# 10x15_Matrix.net
KiCad netlist of a schematic drawn in Altium Designer
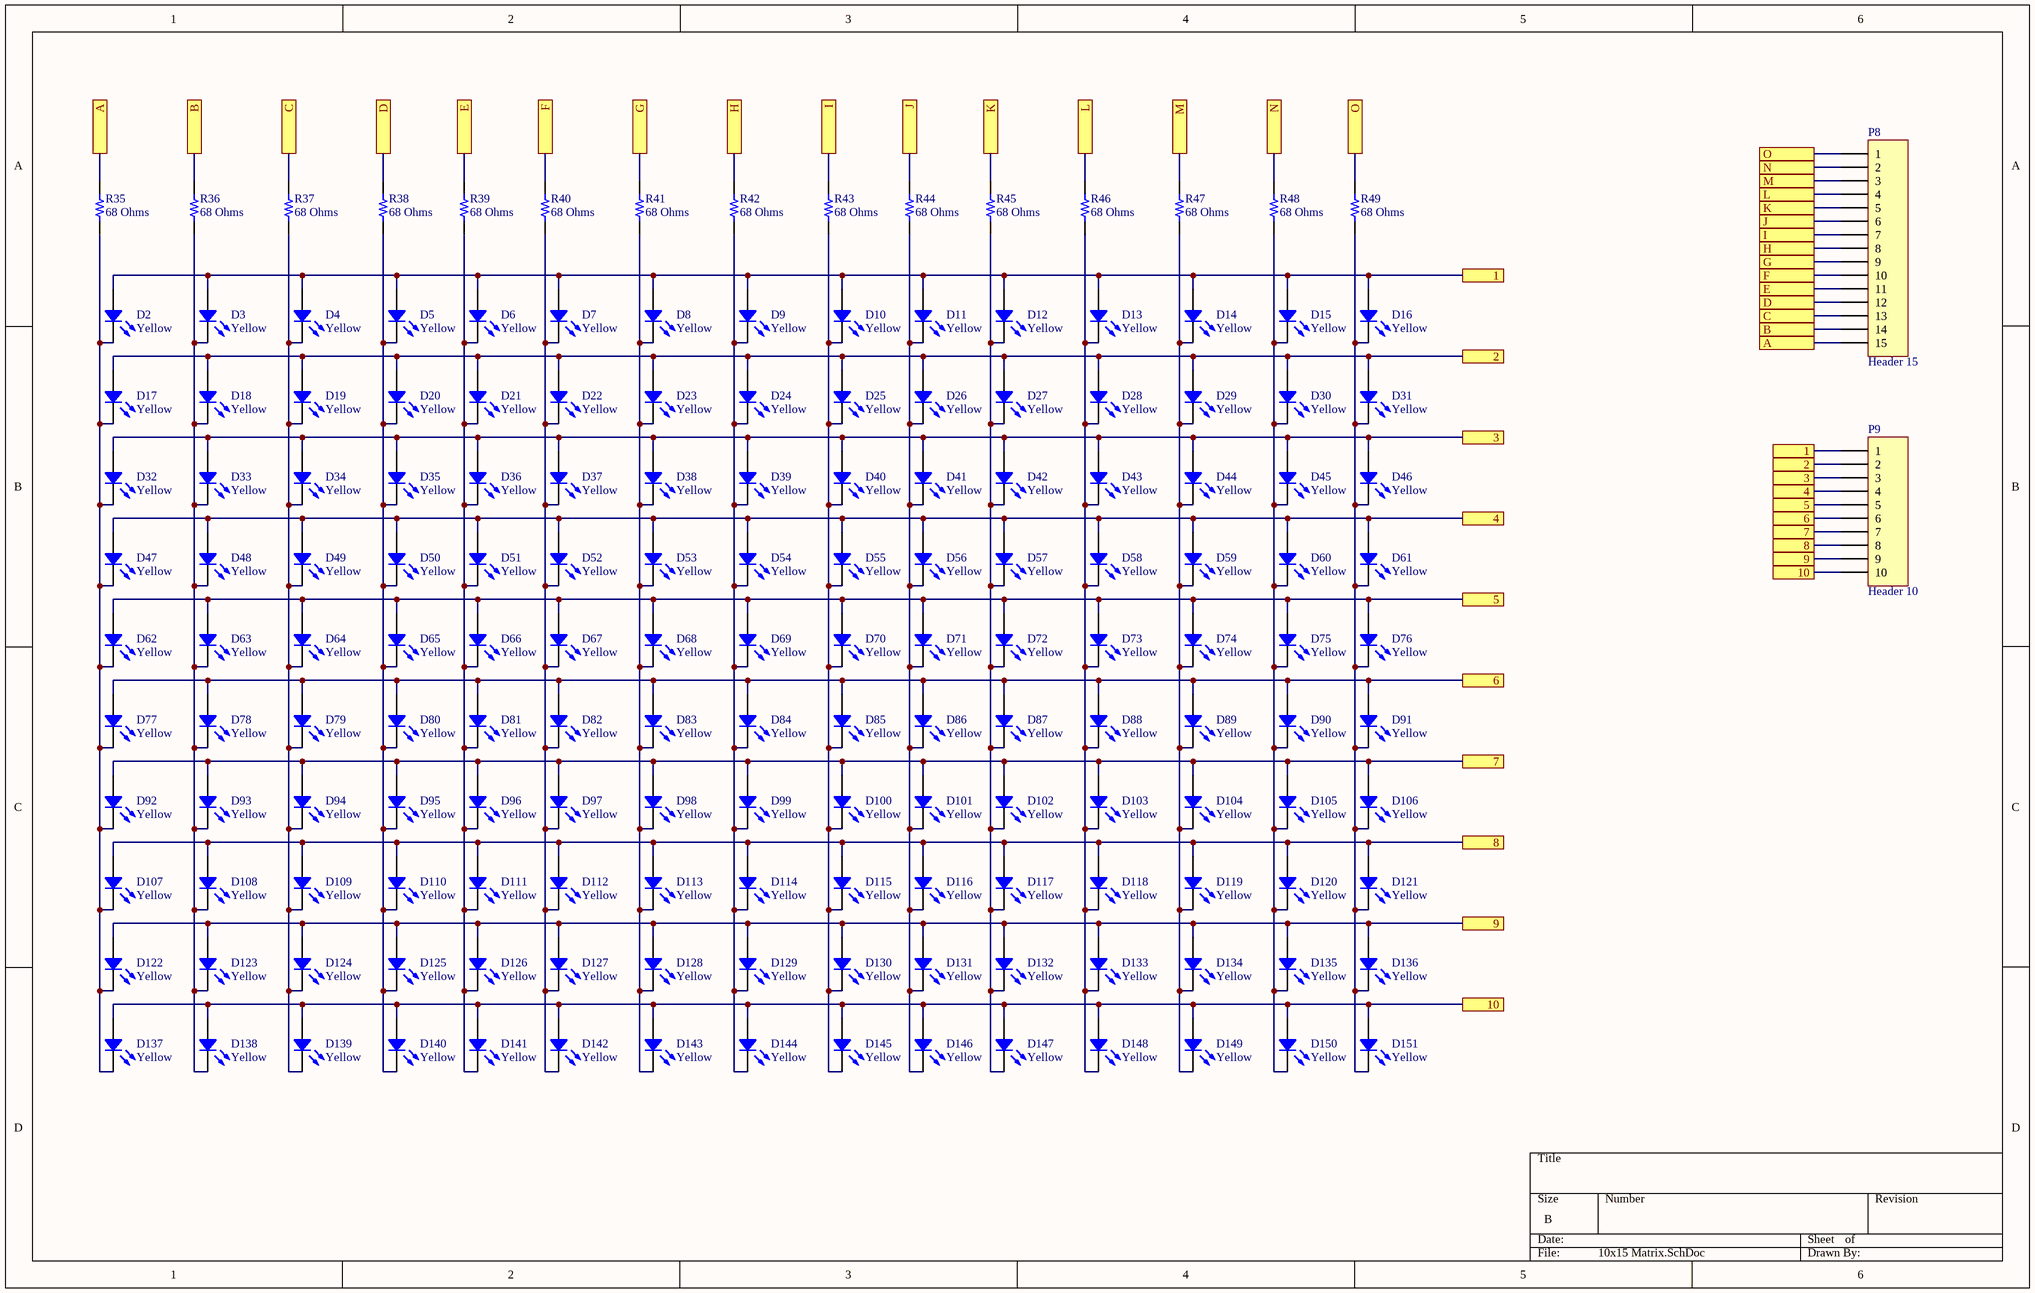
[diagram p0: 10x15 Matrix.SchDoc]

(export (version "E")
  (design (tool "Eeschema 10.0.6"))
  (components
    (comp (ref "D2")
      (value "Yellow")
      (footprint "LED 0805_2012 YELLOW")
      (description "LED YELLOW CLEAR SMD")
      (fields
        (field (name "PART NUMBER") "SML-LX0805YC-TR")
        (field (name "MANUFACTURER") "Lumex Opto/Components Inc.")
      )
      (libsource (lib "Celestial Altium Library - altium_library") (part "LED"))
    )
    (comp (ref "D3")
      (value "Yellow")
      (footprint "LED 0805_2012 YELLOW")
      (description "LED YELLOW CLEAR SMD")
      (fields
        (field (name "PART NUMBER") "SML-LX0805YC-TR")
        (field (name "MANUFACTURER") "Lumex Opto/Components Inc.")
      )
      (libsource (lib "Celestial Altium Library - altium_library") (part "LED"))
    )
    (comp (ref "D4")
      (value "Yellow")
      (footprint "LED 0805_2012 YELLOW")
      (description "LED YELLOW CLEAR SMD")
      (fields
        (field (name "PART NUMBER") "SML-LX0805YC-TR")
        (field (name "MANUFACTURER") "Lumex Opto/Components Inc.")
      )
      (libsource (lib "Celestial Altium Library - altium_library") (part "LED"))
    )
    (comp (ref "D5")
      (value "Yellow")
      (footprint "LED 0805_2012 YELLOW")
      (description "LED YELLOW CLEAR SMD")
      (fields
        (field (name "PART NUMBER") "SML-LX0805YC-TR")
        (field (name "MANUFACTURER") "Lumex Opto/Components Inc.")
      )
      (libsource (lib "Celestial Altium Library - altium_library") (part "LED"))
    )
    (comp (ref "D6")
      (value "Yellow")
      (footprint "LED 0805_2012 YELLOW")
      (description "LED YELLOW CLEAR SMD")
      (fields
        (field (name "PART NUMBER") "SML-LX0805YC-TR")
        (field (name "MANUFACTURER") "Lumex Opto/Components Inc.")
      )
      (libsource (lib "Celestial Altium Library - altium_library") (part "LED"))
    )
    (comp (ref "D7")
      (value "Yellow")
      (footprint "LED 0805_2012 YELLOW")
      (description "LED YELLOW CLEAR SMD")
      (fields
        (field (name "PART NUMBER") "SML-LX0805YC-TR")
        (field (name "MANUFACTURER") "Lumex Opto/Components Inc.")
      )
      (libsource (lib "Celestial Altium Library - altium_library") (part "LED"))
    )
    (comp (ref "D8")
      (value "Yellow")
      (footprint "LED 0805_2012 YELLOW")
      (description "LED YELLOW CLEAR SMD")
      (fields
        (field (name "PART NUMBER") "SML-LX0805YC-TR")
        (field (name "MANUFACTURER") "Lumex Opto/Components Inc.")
      )
      (libsource (lib "Celestial Altium Library - altium_library") (part "LED"))
    )
    (comp (ref "D9")
      (value "Yellow")
      (footprint "LED 0805_2012 YELLOW")
      (description "LED YELLOW CLEAR SMD")
      (fields
        (field (name "PART NUMBER") "SML-LX0805YC-TR")
        (field (name "MANUFACTURER") "Lumex Opto/Components Inc.")
      )
      (libsource (lib "Celestial Altium Library - altium_library") (part "LED"))
    )
    (comp (ref "D10")
      (value "Yellow")
      (footprint "LED 0805_2012 YELLOW")
      (description "LED YELLOW CLEAR SMD")
      (fields
        (field (name "PART NUMBER") "SML-LX0805YC-TR")
        (field (name "MANUFACTURER") "Lumex Opto/Components Inc.")
      )
      (libsource (lib "Celestial Altium Library - altium_library") (part "LED"))
    )
    (comp (ref "D11")
      (value "Yellow")
      (footprint "LED 0805_2012 YELLOW")
      (description "LED YELLOW CLEAR SMD")
      (fields
        (field (name "PART NUMBER") "SML-LX0805YC-TR")
        (field (name "MANUFACTURER") "Lumex Opto/Components Inc.")
      )
      (libsource (lib "Celestial Altium Library - altium_library") (part "LED"))
    )
    (comp (ref "D12")
      (value "Yellow")
      (footprint "LED 0805_2012 YELLOW")
      (description "LED YELLOW CLEAR SMD")
      (fields
        (field (name "PART NUMBER") "SML-LX0805YC-TR")
        (field (name "MANUFACTURER") "Lumex Opto/Components Inc.")
      )
      (libsource (lib "Celestial Altium Library - altium_library") (part "LED"))
    )
    (comp (ref "D13")
      (value "Yellow")
      (footprint "LED 0805_2012 YELLOW")
      (description "LED YELLOW CLEAR SMD")
      (fields
        (field (name "PART NUMBER") "SML-LX0805YC-TR")
        (field (name "MANUFACTURER") "Lumex Opto/Components Inc.")
      )
      (libsource (lib "Celestial Altium Library - altium_library") (part "LED"))
    )
    (comp (ref "D14")
      (value "Yellow")
      (footprint "LED 0805_2012 YELLOW")
      (description "LED YELLOW CLEAR SMD")
      (fields
        (field (name "PART NUMBER") "SML-LX0805YC-TR")
        (field (name "MANUFACTURER") "Lumex Opto/Components Inc.")
      )
      (libsource (lib "Celestial Altium Library - altium_library") (part "LED"))
    )
    (comp (ref "D15")
      (value "Yellow")
      (footprint "LED 0805_2012 YELLOW")
      (description "LED YELLOW CLEAR SMD")
      (fields
        (field (name "PART NUMBER") "SML-LX0805YC-TR")
        (field (name "MANUFACTURER") "Lumex Opto/Components Inc.")
      )
      (libsource (lib "Celestial Altium Library - altium_library") (part "LED"))
    )
    (comp (ref "D16")
      (value "Yellow")
      (footprint "LED 0805_2012 YELLOW")
      (description "LED YELLOW CLEAR SMD")
      (fields
        (field (name "PART NUMBER") "SML-LX0805YC-TR")
        (field (name "MANUFACTURER") "Lumex Opto/Components Inc.")
      )
      (libsource (lib "Celestial Altium Library - altium_library") (part "LED"))
    )
    (comp (ref "D17")
      (value "Yellow")
      (footprint "LED 0805_2012 YELLOW")
      (description "LED YELLOW CLEAR SMD")
      (fields
        (field (name "PART NUMBER") "SML-LX0805YC-TR")
        (field (name "MANUFACTURER") "Lumex Opto/Components Inc.")
      )
      (libsource (lib "Celestial Altium Library - altium_library") (part "LED"))
    )
    (comp (ref "D18")
      (value "Yellow")
      (footprint "LED 0805_2012 YELLOW")
      (description "LED YELLOW CLEAR SMD")
      (fields
        (field (name "PART NUMBER") "SML-LX0805YC-TR")
        (field (name "MANUFACTURER") "Lumex Opto/Components Inc.")
      )
      (libsource (lib "Celestial Altium Library - altium_library") (part "LED"))
    )
    (comp (ref "D19")
      (value "Yellow")
      (footprint "LED 0805_2012 YELLOW")
      (description "LED YELLOW CLEAR SMD")
      (fields
        (field (name "PART NUMBER") "SML-LX0805YC-TR")
        (field (name "MANUFACTURER") "Lumex Opto/Components Inc.")
      )
      (libsource (lib "Celestial Altium Library - altium_library") (part "LED"))
    )
    (comp (ref "D20")
      (value "Yellow")
      (footprint "LED 0805_2012 YELLOW")
      (description "LED YELLOW CLEAR SMD")
      (fields
        (field (name "PART NUMBER") "SML-LX0805YC-TR")
        (field (name "MANUFACTURER") "Lumex Opto/Components Inc.")
      )
      (libsource (lib "Celestial Altium Library - altium_library") (part "LED"))
    )
    (comp (ref "D21")
      (value "Yellow")
      (footprint "LED 0805_2012 YELLOW")
      (description "LED YELLOW CLEAR SMD")
      (fields
        (field (name "PART NUMBER") "SML-LX0805YC-TR")
        (field (name "MANUFACTURER") "Lumex Opto/Components Inc.")
      )
      (libsource (lib "Celestial Altium Library - altium_library") (part "LED"))
    )
    (comp (ref "D22")
      (value "Yellow")
      (footprint "LED 0805_2012 YELLOW")
      (description "LED YELLOW CLEAR SMD")
      (fields
        (field (name "PART NUMBER") "SML-LX0805YC-TR")
        (field (name "MANUFACTURER") "Lumex Opto/Components Inc.")
      )
      (libsource (lib "Celestial Altium Library - altium_library") (part "LED"))
    )
    (comp (ref "D23")
      (value "Yellow")
      (footprint "LED 0805_2012 YELLOW")
      (description "LED YELLOW CLEAR SMD")
      (fields
        (field (name "PART NUMBER") "SML-LX0805YC-TR")
        (field (name "MANUFACTURER") "Lumex Opto/Components Inc.")
      )
      (libsource (lib "Celestial Altium Library - altium_library") (part "LED"))
    )
    (comp (ref "D24")
      (value "Yellow")
      (footprint "LED 0805_2012 YELLOW")
      (description "LED YELLOW CLEAR SMD")
      (fields
        (field (name "PART NUMBER") "SML-LX0805YC-TR")
        (field (name "MANUFACTURER") "Lumex Opto/Components Inc.")
      )
      (libsource (lib "Celestial Altium Library - altium_library") (part "LED"))
    )
    (comp (ref "D25")
      (value "Yellow")
      (footprint "LED 0805_2012 YELLOW")
      (description "LED YELLOW CLEAR SMD")
      (fields
        (field (name "PART NUMBER") "SML-LX0805YC-TR")
        (field (name "MANUFACTURER") "Lumex Opto/Components Inc.")
      )
      (libsource (lib "Celestial Altium Library - altium_library") (part "LED"))
    )
    (comp (ref "D26")
      (value "Yellow")
      (footprint "LED 0805_2012 YELLOW")
      (description "LED YELLOW CLEAR SMD")
      (fields
        (field (name "PART NUMBER") "SML-LX0805YC-TR")
        (field (name "MANUFACTURER") "Lumex Opto/Components Inc.")
      )
      (libsource (lib "Celestial Altium Library - altium_library") (part "LED"))
    )
    (comp (ref "D27")
      (value "Yellow")
      (footprint "LED 0805_2012 YELLOW")
      (description "LED YELLOW CLEAR SMD")
      (fields
        (field (name "PART NUMBER") "SML-LX0805YC-TR")
        (field (name "MANUFACTURER") "Lumex Opto/Components Inc.")
      )
      (libsource (lib "Celestial Altium Library - altium_library") (part "LED"))
    )
    (comp (ref "D28")
      (value "Yellow")
      (footprint "LED 0805_2012 YELLOW")
      (description "LED YELLOW CLEAR SMD")
      (fields
        (field (name "PART NUMBER") "SML-LX0805YC-TR")
        (field (name "MANUFACTURER") "Lumex Opto/Components Inc.")
      )
      (libsource (lib "Celestial Altium Library - altium_library") (part "LED"))
    )
    (comp (ref "D29")
      (value "Yellow")
      (footprint "LED 0805_2012 YELLOW")
      (description "LED YELLOW CLEAR SMD")
      (fields
        (field (name "PART NUMBER") "SML-LX0805YC-TR")
        (field (name "MANUFACTURER") "Lumex Opto/Components Inc.")
      )
      (libsource (lib "Celestial Altium Library - altium_library") (part "LED"))
    )
    (comp (ref "D30")
      (value "Yellow")
      (footprint "LED 0805_2012 YELLOW")
      (description "LED YELLOW CLEAR SMD")
      (fields
        (field (name "PART NUMBER") "SML-LX0805YC-TR")
        (field (name "MANUFACTURER") "Lumex Opto/Components Inc.")
      )
      (libsource (lib "Celestial Altium Library - altium_library") (part "LED"))
    )
    (comp (ref "D31")
      (value "Yellow")
      (footprint "LED 0805_2012 YELLOW")
      (description "LED YELLOW CLEAR SMD")
      (fields
        (field (name "PART NUMBER") "SML-LX0805YC-TR")
        (field (name "MANUFACTURER") "Lumex Opto/Components Inc.")
      )
      (libsource (lib "Celestial Altium Library - altium_library") (part "LED"))
    )
    (comp (ref "D32")
      (value "Yellow")
      (footprint "LED 0805_2012 YELLOW")
      (description "LED YELLOW CLEAR SMD")
      (fields
        (field (name "PART NUMBER") "SML-LX0805YC-TR")
        (field (name "MANUFACTURER") "Lumex Opto/Components Inc.")
      )
      (libsource (lib "Celestial Altium Library - altium_library") (part "LED"))
    )
    (comp (ref "D33")
      (value "Yellow")
      (footprint "LED 0805_2012 YELLOW")
      (description "LED YELLOW CLEAR SMD")
      (fields
        (field (name "PART NUMBER") "SML-LX0805YC-TR")
        (field (name "MANUFACTURER") "Lumex Opto/Components Inc.")
      )
      (libsource (lib "Celestial Altium Library - altium_library") (part "LED"))
    )
    (comp (ref "D34")
      (value "Yellow")
      (footprint "LED 0805_2012 YELLOW")
      (description "LED YELLOW CLEAR SMD")
      (fields
        (field (name "PART NUMBER") "SML-LX0805YC-TR")
        (field (name "MANUFACTURER") "Lumex Opto/Components Inc.")
      )
      (libsource (lib "Celestial Altium Library - altium_library") (part "LED"))
    )
    (comp (ref "D35")
      (value "Yellow")
      (footprint "LED 0805_2012 YELLOW")
      (description "LED YELLOW CLEAR SMD")
      (fields
        (field (name "PART NUMBER") "SML-LX0805YC-TR")
        (field (name "MANUFACTURER") "Lumex Opto/Components Inc.")
      )
      (libsource (lib "Celestial Altium Library - altium_library") (part "LED"))
    )
    (comp (ref "D36")
      (value "Yellow")
      (footprint "LED 0805_2012 YELLOW")
      (description "LED YELLOW CLEAR SMD")
      (fields
        (field (name "PART NUMBER") "SML-LX0805YC-TR")
        (field (name "MANUFACTURER") "Lumex Opto/Components Inc.")
      )
      (libsource (lib "Celestial Altium Library - altium_library") (part "LED"))
    )
    (comp (ref "D37")
      (value "Yellow")
      (footprint "LED 0805_2012 YELLOW")
      (description "LED YELLOW CLEAR SMD")
      (fields
        (field (name "PART NUMBER") "SML-LX0805YC-TR")
        (field (name "MANUFACTURER") "Lumex Opto/Components Inc.")
      )
      (libsource (lib "Celestial Altium Library - altium_library") (part "LED"))
    )
    (comp (ref "D38")
      (value "Yellow")
      (footprint "LED 0805_2012 YELLOW")
      (description "LED YELLOW CLEAR SMD")
      (fields
        (field (name "PART NUMBER") "SML-LX0805YC-TR")
        (field (name "MANUFACTURER") "Lumex Opto/Components Inc.")
      )
      (libsource (lib "Celestial Altium Library - altium_library") (part "LED"))
    )
    (comp (ref "D39")
      (value "Yellow")
      (footprint "LED 0805_2012 YELLOW")
      (description "LED YELLOW CLEAR SMD")
      (fields
        (field (name "PART NUMBER") "SML-LX0805YC-TR")
        (field (name "MANUFACTURER") "Lumex Opto/Components Inc.")
      )
      (libsource (lib "Celestial Altium Library - altium_library") (part "LED"))
    )
    (comp (ref "D40")
      (value "Yellow")
      (footprint "LED 0805_2012 YELLOW")
      (description "LED YELLOW CLEAR SMD")
      (fields
        (field (name "PART NUMBER") "SML-LX0805YC-TR")
        (field (name "MANUFACTURER") "Lumex Opto/Components Inc.")
      )
      (libsource (lib "Celestial Altium Library - altium_library") (part "LED"))
    )
    (comp (ref "D41")
      (value "Yellow")
      (footprint "LED 0805_2012 YELLOW")
      (description "LED YELLOW CLEAR SMD")
      (fields
        (field (name "PART NUMBER") "SML-LX0805YC-TR")
        (field (name "MANUFACTURER") "Lumex Opto/Components Inc.")
      )
      (libsource (lib "Celestial Altium Library - altium_library") (part "LED"))
    )
    (comp (ref "D42")
      (value "Yellow")
      (footprint "LED 0805_2012 YELLOW")
      (description "LED YELLOW CLEAR SMD")
      (fields
        (field (name "PART NUMBER") "SML-LX0805YC-TR")
        (field (name "MANUFACTURER") "Lumex Opto/Components Inc.")
      )
      (libsource (lib "Celestial Altium Library - altium_library") (part "LED"))
    )
    (comp (ref "D43")
      (value "Yellow")
      (footprint "LED 0805_2012 YELLOW")
      (description "LED YELLOW CLEAR SMD")
      (fields
        (field (name "PART NUMBER") "SML-LX0805YC-TR")
        (field (name "MANUFACTURER") "Lumex Opto/Components Inc.")
      )
      (libsource (lib "Celestial Altium Library - altium_library") (part "LED"))
    )
    (comp (ref "D44")
      (value "Yellow")
      (footprint "LED 0805_2012 YELLOW")
      (description "LED YELLOW CLEAR SMD")
      (fields
        (field (name "PART NUMBER") "SML-LX0805YC-TR")
        (field (name "MANUFACTURER") "Lumex Opto/Components Inc.")
      )
      (libsource (lib "Celestial Altium Library - altium_library") (part "LED"))
    )
    (comp (ref "D45")
      (value "Yellow")
      (footprint "LED 0805_2012 YELLOW")
      (description "LED YELLOW CLEAR SMD")
      (fields
        (field (name "PART NUMBER") "SML-LX0805YC-TR")
        (field (name "MANUFACTURER") "Lumex Opto/Components Inc.")
      )
      (libsource (lib "Celestial Altium Library - altium_library") (part "LED"))
    )
    (comp (ref "D46")
      (value "Yellow")
      (footprint "LED 0805_2012 YELLOW")
      (description "LED YELLOW CLEAR SMD")
      (fields
        (field (name "PART NUMBER") "SML-LX0805YC-TR")
        (field (name "MANUFACTURER") "Lumex Opto/Components Inc.")
      )
      (libsource (lib "Celestial Altium Library - altium_library") (part "LED"))
    )
    (comp (ref "D47")
      (value "Yellow")
      (footprint "LED 0805_2012 YELLOW")
      (description "LED YELLOW CLEAR SMD")
      (fields
        (field (name "PART NUMBER") "SML-LX0805YC-TR")
        (field (name "MANUFACTURER") "Lumex Opto/Components Inc.")
      )
      (libsource (lib "Celestial Altium Library - altium_library") (part "LED"))
    )
    (comp (ref "D48")
      (value "Yellow")
      (footprint "LED 0805_2012 YELLOW")
      (description "LED YELLOW CLEAR SMD")
      (fields
        (field (name "PART NUMBER") "SML-LX0805YC-TR")
        (field (name "MANUFACTURER") "Lumex Opto/Components Inc.")
      )
      (libsource (lib "Celestial Altium Library - altium_library") (part "LED"))
    )
    (comp (ref "D49")
      (value "Yellow")
      (footprint "LED 0805_2012 YELLOW")
      (description "LED YELLOW CLEAR SMD")
      (fields
        (field (name "PART NUMBER") "SML-LX0805YC-TR")
        (field (name "MANUFACTURER") "Lumex Opto/Components Inc.")
      )
      (libsource (lib "Celestial Altium Library - altium_library") (part "LED"))
    )
    (comp (ref "D50")
      (value "Yellow")
      (footprint "LED 0805_2012 YELLOW")
      (description "LED YELLOW CLEAR SMD")
      (fields
        (field (name "PART NUMBER") "SML-LX0805YC-TR")
        (field (name "MANUFACTURER") "Lumex Opto/Components Inc.")
      )
      (libsource (lib "Celestial Altium Library - altium_library") (part "LED"))
    )
    (comp (ref "D51")
      (value "Yellow")
      (footprint "LED 0805_2012 YELLOW")
      (description "LED YELLOW CLEAR SMD")
      (fields
        (field (name "PART NUMBER") "SML-LX0805YC-TR")
        (field (name "MANUFACTURER") "Lumex Opto/Components Inc.")
      )
      (libsource (lib "Celestial Altium Library - altium_library") (part "LED"))
    )
    (comp (ref "D52")
      (value "Yellow")
      (footprint "LED 0805_2012 YELLOW")
      (description "LED YELLOW CLEAR SMD")
      (fields
        (field (name "PART NUMBER") "SML-LX0805YC-TR")
        (field (name "MANUFACTURER") "Lumex Opto/Components Inc.")
      )
      (libsource (lib "Celestial Altium Library - altium_library") (part "LED"))
    )
    (comp (ref "D53")
      (value "Yellow")
      (footprint "LED 0805_2012 YELLOW")
      (description "LED YELLOW CLEAR SMD")
      (fields
        (field (name "PART NUMBER") "SML-LX0805YC-TR")
        (field (name "MANUFACTURER") "Lumex Opto/Components Inc.")
      )
      (libsource (lib "Celestial Altium Library - altium_library") (part "LED"))
    )
    (comp (ref "D54")
      (value "Yellow")
      (footprint "LED 0805_2012 YELLOW")
      (description "LED YELLOW CLEAR SMD")
      (fields
        (field (name "PART NUMBER") "SML-LX0805YC-TR")
        (field (name "MANUFACTURER") "Lumex Opto/Components Inc.")
      )
      (libsource (lib "Celestial Altium Library - altium_library") (part "LED"))
    )
    (comp (ref "D55")
      (value "Yellow")
      (footprint "LED 0805_2012 YELLOW")
      (description "LED YELLOW CLEAR SMD")
      (fields
        (field (name "PART NUMBER") "SML-LX0805YC-TR")
        (field (name "MANUFACTURER") "Lumex Opto/Components Inc.")
      )
      (libsource (lib "Celestial Altium Library - altium_library") (part "LED"))
    )
    (comp (ref "D56")
      (value "Yellow")
      (footprint "LED 0805_2012 YELLOW")
      (description "LED YELLOW CLEAR SMD")
      (fields
        (field (name "PART NUMBER") "SML-LX0805YC-TR")
        (field (name "MANUFACTURER") "Lumex Opto/Components Inc.")
      )
      (libsource (lib "Celestial Altium Library - altium_library") (part "LED"))
    )
    (comp (ref "D57")
      (value "Yellow")
      (footprint "LED 0805_2012 YELLOW")
      (description "LED YELLOW CLEAR SMD")
      (fields
        (field (name "PART NUMBER") "SML-LX0805YC-TR")
        (field (name "MANUFACTURER") "Lumex Opto/Components Inc.")
      )
      (libsource (lib "Celestial Altium Library - altium_library") (part "LED"))
    )
    (comp (ref "D58")
      (value "Yellow")
      (footprint "LED 0805_2012 YELLOW")
      (description "LED YELLOW CLEAR SMD")
      (fields
        (field (name "PART NUMBER") "SML-LX0805YC-TR")
        (field (name "MANUFACTURER") "Lumex Opto/Components Inc.")
      )
      (libsource (lib "Celestial Altium Library - altium_library") (part "LED"))
    )
    (comp (ref "D59")
      (value "Yellow")
      (footprint "LED 0805_2012 YELLOW")
      (description "LED YELLOW CLEAR SMD")
      (fields
        (field (name "PART NUMBER") "SML-LX0805YC-TR")
        (field (name "MANUFACTURER") "Lumex Opto/Components Inc.")
      )
      (libsource (lib "Celestial Altium Library - altium_library") (part "LED"))
    )
    (comp (ref "D60")
      (value "Yellow")
      (footprint "LED 0805_2012 YELLOW")
      (description "LED YELLOW CLEAR SMD")
      (fields
        (field (name "PART NUMBER") "SML-LX0805YC-TR")
        (field (name "MANUFACTURER") "Lumex Opto/Components Inc.")
      )
      (libsource (lib "Celestial Altium Library - altium_library") (part "LED"))
    )
    (comp (ref "D61")
      (value "Yellow")
      (footprint "LED 0805_2012 YELLOW")
      (description "LED YELLOW CLEAR SMD")
      (fields
        (field (name "PART NUMBER") "SML-LX0805YC-TR")
        (field (name "MANUFACTURER") "Lumex Opto/Components Inc.")
      )
      (libsource (lib "Celestial Altium Library - altium_library") (part "LED"))
    )
    (comp (ref "D62")
      (value "Yellow")
      (footprint "LED 0805_2012 YELLOW")
      (description "LED YELLOW CLEAR SMD")
      (fields
        (field (name "PART NUMBER") "SML-LX0805YC-TR")
        (field (name "MANUFACTURER") "Lumex Opto/Components Inc.")
      )
      (libsource (lib "Celestial Altium Library - altium_library") (part "LED"))
    )
    (comp (ref "D63")
      (value "Yellow")
      (footprint "LED 0805_2012 YELLOW")
      (description "LED YELLOW CLEAR SMD")
      (fields
        (field (name "PART NUMBER") "SML-LX0805YC-TR")
        (field (name "MANUFACTURER") "Lumex Opto/Components Inc.")
      )
      (libsource (lib "Celestial Altium Library - altium_library") (part "LED"))
    )
    (comp (ref "D64")
      (value "Yellow")
      (footprint "LED 0805_2012 YELLOW")
      (description "LED YELLOW CLEAR SMD")
      (fields
        (field (name "PART NUMBER") "SML-LX0805YC-TR")
        (field (name "MANUFACTURER") "Lumex Opto/Components Inc.")
      )
      (libsource (lib "Celestial Altium Library - altium_library") (part "LED"))
    )
    (comp (ref "D65")
      (value "Yellow")
      (footprint "LED 0805_2012 YELLOW")
      (description "LED YELLOW CLEAR SMD")
      (fields
        (field (name "PART NUMBER") "SML-LX0805YC-TR")
        (field (name "MANUFACTURER") "Lumex Opto/Components Inc.")
      )
      (libsource (lib "Celestial Altium Library - altium_library") (part "LED"))
    )
    (comp (ref "D66")
      (value "Yellow")
      (footprint "LED 0805_2012 YELLOW")
      (description "LED YELLOW CLEAR SMD")
      (fields
        (field (name "PART NUMBER") "SML-LX0805YC-TR")
        (field (name "MANUFACTURER") "Lumex Opto/Components Inc.")
      )
      (libsource (lib "Celestial Altium Library - altium_library") (part "LED"))
    )
    (comp (ref "D67")
      (value "Yellow")
      (footprint "LED 0805_2012 YELLOW")
      (description "LED YELLOW CLEAR SMD")
      (fields
        (field (name "PART NUMBER") "SML-LX0805YC-TR")
        (field (name "MANUFACTURER") "Lumex Opto/Components Inc.")
      )
      (libsource (lib "Celestial Altium Library - altium_library") (part "LED"))
    )
    (comp (ref "D68")
      (value "Yellow")
      (footprint "LED 0805_2012 YELLOW")
      (description "LED YELLOW CLEAR SMD")
      (fields
        (field (name "PART NUMBER") "SML-LX0805YC-TR")
        (field (name "MANUFACTURER") "Lumex Opto/Components Inc.")
      )
      (libsource (lib "Celestial Altium Library - altium_library") (part "LED"))
    )
    (comp (ref "D69")
      (value "Yellow")
      (footprint "LED 0805_2012 YELLOW")
      (description "LED YELLOW CLEAR SMD")
      (fields
        (field (name "PART NUMBER") "SML-LX0805YC-TR")
        (field (name "MANUFACTURER") "Lumex Opto/Components Inc.")
      )
      (libsource (lib "Celestial Altium Library - altium_library") (part "LED"))
    )
    (comp (ref "D70")
      (value "Yellow")
      (footprint "LED 0805_2012 YELLOW")
      (description "LED YELLOW CLEAR SMD")
      (fields
        (field (name "PART NUMBER") "SML-LX0805YC-TR")
        (field (name "MANUFACTURER") "Lumex Opto/Components Inc.")
      )
      (libsource (lib "Celestial Altium Library - altium_library") (part "LED"))
    )
    (comp (ref "D71")
      (value "Yellow")
      (footprint "LED 0805_2012 YELLOW")
      (description "LED YELLOW CLEAR SMD")
      (fields
        (field (name "PART NUMBER") "SML-LX0805YC-TR")
        (field (name "MANUFACTURER") "Lumex Opto/Components Inc.")
      )
      (libsource (lib "Celestial Altium Library - altium_library") (part "LED"))
    )
    (comp (ref "D72")
      (value "Yellow")
      (footprint "LED 0805_2012 YELLOW")
      (description "LED YELLOW CLEAR SMD")
      (fields
        (field (name "PART NUMBER") "SML-LX0805YC-TR")
        (field (name "MANUFACTURER") "Lumex Opto/Components Inc.")
      )
      (libsource (lib "Celestial Altium Library - altium_library") (part "LED"))
    )
    (comp (ref "D73")
      (value "Yellow")
      (footprint "LED 0805_2012 YELLOW")
      (description "LED YELLOW CLEAR SMD")
      (fields
        (field (name "PART NUMBER") "SML-LX0805YC-TR")
        (field (name "MANUFACTURER") "Lumex Opto/Components Inc.")
      )
      (libsource (lib "Celestial Altium Library - altium_library") (part "LED"))
    )
    (comp (ref "D74")
      (value "Yellow")
      (footprint "LED 0805_2012 YELLOW")
      (description "LED YELLOW CLEAR SMD")
      (fields
        (field (name "PART NUMBER") "SML-LX0805YC-TR")
        (field (name "MANUFACTURER") "Lumex Opto/Components Inc.")
      )
      (libsource (lib "Celestial Altium Library - altium_library") (part "LED"))
    )
    (comp (ref "D75")
      (value "Yellow")
      (footprint "LED 0805_2012 YELLOW")
      (description "LED YELLOW CLEAR SMD")
      (fields
        (field (name "PART NUMBER") "SML-LX0805YC-TR")
        (field (name "MANUFACTURER") "Lumex Opto/Components Inc.")
      )
      (libsource (lib "Celestial Altium Library - altium_library") (part "LED"))
    )
    (comp (ref "D76")
      (value "Yellow")
      (footprint "LED 0805_2012 YELLOW")
      (description "LED YELLOW CLEAR SMD")
      (fields
        (field (name "PART NUMBER") "SML-LX0805YC-TR")
        (field (name "MANUFACTURER") "Lumex Opto/Components Inc.")
      )
      (libsource (lib "Celestial Altium Library - altium_library") (part "LED"))
    )
    (comp (ref "D77")
      (value "Yellow")
      (footprint "LED 0805_2012 YELLOW")
      (description "LED YELLOW CLEAR SMD")
      (fields
        (field (name "PART NUMBER") "SML-LX0805YC-TR")
        (field (name "MANUFACTURER") "Lumex Opto/Components Inc.")
      )
      (libsource (lib "Celestial Altium Library - altium_library") (part "LED"))
    )
    (comp (ref "D78")
      (value "Yellow")
      (footprint "LED 0805_2012 YELLOW")
      (description "LED YELLOW CLEAR SMD")
      (fields
        (field (name "PART NUMBER") "SML-LX0805YC-TR")
        (field (name "MANUFACTURER") "Lumex Opto/Components Inc.")
      )
      (libsource (lib "Celestial Altium Library - altium_library") (part "LED"))
    )
    (comp (ref "D79")
      (value "Yellow")
      (footprint "LED 0805_2012 YELLOW")
      (description "LED YELLOW CLEAR SMD")
      (fields
        (field (name "PART NUMBER") "SML-LX0805YC-TR")
        (field (name "MANUFACTURER") "Lumex Opto/Components Inc.")
      )
      (libsource (lib "Celestial Altium Library - altium_library") (part "LED"))
    )
    (comp (ref "D80")
      (value "Yellow")
      (footprint "LED 0805_2012 YELLOW")
      (description "LED YELLOW CLEAR SMD")
      (fields
        (field (name "PART NUMBER") "SML-LX0805YC-TR")
        (field (name "MANUFACTURER") "Lumex Opto/Components Inc.")
      )
      (libsource (lib "Celestial Altium Library - altium_library") (part "LED"))
    )
    (comp (ref "D81")
      (value "Yellow")
      (footprint "LED 0805_2012 YELLOW")
      (description "LED YELLOW CLEAR SMD")
      (fields
        (field (name "PART NUMBER") "SML-LX0805YC-TR")
        (field (name "MANUFACTURER") "Lumex Opto/Components Inc.")
      )
      (libsource (lib "Celestial Altium Library - altium_library") (part "LED"))
    )
    (comp (ref "D82")
      (value "Yellow")
      (footprint "LED 0805_2012 YELLOW")
      (description "LED YELLOW CLEAR SMD")
      (fields
        (field (name "PART NUMBER") "SML-LX0805YC-TR")
        (field (name "MANUFACTURER") "Lumex Opto/Components Inc.")
      )
      (libsource (lib "Celestial Altium Library - altium_library") (part "LED"))
    )
    (comp (ref "D83")
      (value "Yellow")
      (footprint "LED 0805_2012 YELLOW")
      (description "LED YELLOW CLEAR SMD")
      (fields
        (field (name "PART NUMBER") "SML-LX0805YC-TR")
        (field (name "MANUFACTURER") "Lumex Opto/Components Inc.")
      )
      (libsource (lib "Celestial Altium Library - altium_library") (part "LED"))
    )
    (comp (ref "D84")
      (value "Yellow")
      (footprint "LED 0805_2012 YELLOW")
      (description "LED YELLOW CLEAR SMD")
      (fields
        (field (name "PART NUMBER") "SML-LX0805YC-TR")
        (field (name "MANUFACTURER") "Lumex Opto/Components Inc.")
      )
      (libsource (lib "Celestial Altium Library - altium_library") (part "LED"))
    )
    (comp (ref "D85")
      (value "Yellow")
      (footprint "LED 0805_2012 YELLOW")
      (description "LED YELLOW CLEAR SMD")
      (fields
        (field (name "PART NUMBER") "SML-LX0805YC-TR")
        (field (name "MANUFACTURER") "Lumex Opto/Components Inc.")
      )
      (libsource (lib "Celestial Altium Library - altium_library") (part "LED"))
    )
    (comp (ref "D86")
      (value "Yellow")
      (footprint "LED 0805_2012 YELLOW")
      (description "LED YELLOW CLEAR SMD")
      (fields
        (field (name "PART NUMBER") "SML-LX0805YC-TR")
        (field (name "MANUFACTURER") "Lumex Opto/Components Inc.")
      )
      (libsource (lib "Celestial Altium Library - altium_library") (part "LED"))
    )
    (comp (ref "D87")
      (value "Yellow")
      (footprint "LED 0805_2012 YELLOW")
      (description "LED YELLOW CLEAR SMD")
      (fields
        (field (name "PART NUMBER") "SML-LX0805YC-TR")
        (field (name "MANUFACTURER") "Lumex Opto/Components Inc.")
      )
      (libsource (lib "Celestial Altium Library - altium_library") (part "LED"))
    )
    (comp (ref "D88")
      (value "Yellow")
      (footprint "LED 0805_2012 YELLOW")
      (description "LED YELLOW CLEAR SMD")
      (fields
        (field (name "PART NUMBER") "SML-LX0805YC-TR")
        (field (name "MANUFACTURER") "Lumex Opto/Components Inc.")
      )
      (libsource (lib "Celestial Altium Library - altium_library") (part "LED"))
    )
    (comp (ref "D89")
      (value "Yellow")
      (footprint "LED 0805_2012 YELLOW")
      (description "LED YELLOW CLEAR SMD")
      (fields
        (field (name "PART NUMBER") "SML-LX0805YC-TR")
        (field (name "MANUFACTURER") "Lumex Opto/Components Inc.")
      )
      (libsource (lib "Celestial Altium Library - altium_library") (part "LED"))
    )
    (comp (ref "D90")
      (value "Yellow")
      (footprint "LED 0805_2012 YELLOW")
      (description "LED YELLOW CLEAR SMD")
      (fields
        (field (name "PART NUMBER") "SML-LX0805YC-TR")
        (field (name "MANUFACTURER") "Lumex Opto/Components Inc.")
      )
      (libsource (lib "Celestial Altium Library - altium_library") (part "LED"))
    )
    (comp (ref "D91")
      (value "Yellow")
      (footprint "LED 0805_2012 YELLOW")
      (description "LED YELLOW CLEAR SMD")
      (fields
        (field (name "PART NUMBER") "SML-LX0805YC-TR")
        (field (name "MANUFACTURER") "Lumex Opto/Components Inc.")
      )
      (libsource (lib "Celestial Altium Library - altium_library") (part "LED"))
    )
    (comp (ref "D92")
      (value "Yellow")
      (footprint "LED 0805_2012 YELLOW")
      (description "LED YELLOW CLEAR SMD")
      (fields
        (field (name "PART NUMBER") "SML-LX0805YC-TR")
        (field (name "MANUFACTURER") "Lumex Opto/Components Inc.")
      )
      (libsource (lib "Celestial Altium Library - altium_library") (part "LED"))
    )
    (comp (ref "D93")
      (value "Yellow")
      (footprint "LED 0805_2012 YELLOW")
      (description "LED YELLOW CLEAR SMD")
      (fields
        (field (name "PART NUMBER") "SML-LX0805YC-TR")
        (field (name "MANUFACTURER") "Lumex Opto/Components Inc.")
      )
      (libsource (lib "Celestial Altium Library - altium_library") (part "LED"))
    )
    (comp (ref "D94")
      (value "Yellow")
      (footprint "LED 0805_2012 YELLOW")
      (description "LED YELLOW CLEAR SMD")
      (fields
        (field (name "PART NUMBER") "SML-LX0805YC-TR")
        (field (name "MANUFACTURER") "Lumex Opto/Components Inc.")
      )
      (libsource (lib "Celestial Altium Library - altium_library") (part "LED"))
    )
    (comp (ref "D95")
      (value "Yellow")
      (footprint "LED 0805_2012 YELLOW")
      (description "LED YELLOW CLEAR SMD")
      (fields
        (field (name "PART NUMBER") "SML-LX0805YC-TR")
        (field (name "MANUFACTURER") "Lumex Opto/Components Inc.")
      )
      (libsource (lib "Celestial Altium Library - altium_library") (part "LED"))
    )
    (comp (ref "D96")
      (value "Yellow")
      (footprint "LED 0805_2012 YELLOW")
      (description "LED YELLOW CLEAR SMD")
      (fields
        (field (name "PART NUMBER") "SML-LX0805YC-TR")
        (field (name "MANUFACTURER") "Lumex Opto/Components Inc.")
      )
      (libsource (lib "Celestial Altium Library - altium_library") (part "LED"))
    )
    (comp (ref "D97")
      (value "Yellow")
      (footprint "LED 0805_2012 YELLOW")
      (description "LED YELLOW CLEAR SMD")
      (fields
        (field (name "PART NUMBER") "SML-LX0805YC-TR")
        (field (name "MANUFACTURER") "Lumex Opto/Components Inc.")
      )
      (libsource (lib "Celestial Altium Library - altium_library") (part "LED"))
    )
    (comp (ref "D98")
      (value "Yellow")
      (footprint "LED 0805_2012 YELLOW")
      (description "LED YELLOW CLEAR SMD")
      (fields
        (field (name "PART NUMBER") "SML-LX0805YC-TR")
        (field (name "MANUFACTURER") "Lumex Opto/Components Inc.")
      )
      (libsource (lib "Celestial Altium Library - altium_library") (part "LED"))
    )
    (comp (ref "D99")
      (value "Yellow")
      (footprint "LED 0805_2012 YELLOW")
      (description "LED YELLOW CLEAR SMD")
      (fields
        (field (name "PART NUMBER") "SML-LX0805YC-TR")
        (field (name "MANUFACTURER") "Lumex Opto/Components Inc.")
      )
      (libsource (lib "Celestial Altium Library - altium_library") (part "LED"))
    )
    (comp (ref "D100")
      (value "Yellow")
      (footprint "LED 0805_2012 YELLOW")
      (description "LED YELLOW CLEAR SMD")
      (fields
        (field (name "PART NUMBER") "SML-LX0805YC-TR")
        (field (name "MANUFACTURER") "Lumex Opto/Components Inc.")
      )
      (libsource (lib "Celestial Altium Library - altium_library") (part "LED"))
    )
    (comp (ref "D101")
      (value "Yellow")
      (footprint "LED 0805_2012 YELLOW")
      (description "LED YELLOW CLEAR SMD")
      (fields
        (field (name "PART NUMBER") "SML-LX0805YC-TR")
        (field (name "MANUFACTURER") "Lumex Opto/Components Inc.")
      )
      (libsource (lib "Celestial Altium Library - altium_library") (part "LED"))
    )
    (comp (ref "D102")
      (value "Yellow")
      (footprint "LED 0805_2012 YELLOW")
      (description "LED YELLOW CLEAR SMD")
      (fields
        (field (name "PART NUMBER") "SML-LX0805YC-TR")
        (field (name "MANUFACTURER") "Lumex Opto/Components Inc.")
      )
      (libsource (lib "Celestial Altium Library - altium_library") (part "LED"))
    )
    (comp (ref "D103")
      (value "Yellow")
      (footprint "LED 0805_2012 YELLOW")
      (description "LED YELLOW CLEAR SMD")
      (fields
        (field (name "PART NUMBER") "SML-LX0805YC-TR")
        (field (name "MANUFACTURER") "Lumex Opto/Components Inc.")
      )
      (libsource (lib "Celestial Altium Library - altium_library") (part "LED"))
    )
    (comp (ref "D104")
      (value "Yellow")
      (footprint "LED 0805_2012 YELLOW")
      (description "LED YELLOW CLEAR SMD")
      (fields
        (field (name "PART NUMBER") "SML-LX0805YC-TR")
        (field (name "MANUFACTURER") "Lumex Opto/Components Inc.")
      )
      (libsource (lib "Celestial Altium Library - altium_library") (part "LED"))
    )
    (comp (ref "D105")
      (value "Yellow")
      (footprint "LED 0805_2012 YELLOW")
      (description "LED YELLOW CLEAR SMD")
      (fields
        (field (name "PART NUMBER") "SML-LX0805YC-TR")
        (field (name "MANUFACTURER") "Lumex Opto/Components Inc.")
      )
      (libsource (lib "Celestial Altium Library - altium_library") (part "LED"))
    )
    (comp (ref "D106")
      (value "Yellow")
      (footprint "LED 0805_2012 YELLOW")
      (description "LED YELLOW CLEAR SMD")
      (fields
        (field (name "PART NUMBER") "SML-LX0805YC-TR")
        (field (name "MANUFACTURER") "Lumex Opto/Components Inc.")
      )
      (libsource (lib "Celestial Altium Library - altium_library") (part "LED"))
    )
    (comp (ref "D107")
      (value "Yellow")
      (footprint "LED 0805_2012 YELLOW")
      (description "LED YELLOW CLEAR SMD")
      (fields
        (field (name "PART NUMBER") "SML-LX0805YC-TR")
        (field (name "MANUFACTURER") "Lumex Opto/Components Inc.")
      )
      (libsource (lib "Celestial Altium Library - altium_library") (part "LED"))
    )
    (comp (ref "D108")
      (value "Yellow")
      (footprint "LED 0805_2012 YELLOW")
      (description "LED YELLOW CLEAR SMD")
      (fields
        (field (name "PART NUMBER") "SML-LX0805YC-TR")
        (field (name "MANUFACTURER") "Lumex Opto/Components Inc.")
      )
      (libsource (lib "Celestial Altium Library - altium_library") (part "LED"))
    )
    (comp (ref "D109")
      (value "Yellow")
      (footprint "LED 0805_2012 YELLOW")
      (description "LED YELLOW CLEAR SMD")
      (fields
        (field (name "PART NUMBER") "SML-LX0805YC-TR")
        (field (name "MANUFACTURER") "Lumex Opto/Components Inc.")
      )
      (libsource (lib "Celestial Altium Library - altium_library") (part "LED"))
    )
    (comp (ref "D110")
      (value "Yellow")
      (footprint "LED 0805_2012 YELLOW")
      (description "LED YELLOW CLEAR SMD")
      (fields
        (field (name "PART NUMBER") "SML-LX0805YC-TR")
        (field (name "MANUFACTURER") "Lumex Opto/Components Inc.")
      )
      (libsource (lib "Celestial Altium Library - altium_library") (part "LED"))
    )
    (comp (ref "D111")
      (value "Yellow")
      (footprint "LED 0805_2012 YELLOW")
      (description "LED YELLOW CLEAR SMD")
      (fields
        (field (name "PART NUMBER") "SML-LX0805YC-TR")
        (field (name "MANUFACTURER") "Lumex Opto/Components Inc.")
      )
      (libsource (lib "Celestial Altium Library - altium_library") (part "LED"))
    )
    (comp (ref "D112")
      (value "Yellow")
      (footprint "LED 0805_2012 YELLOW")
      (description "LED YELLOW CLEAR SMD")
      (fields
        (field (name "PART NUMBER") "SML-LX0805YC-TR")
        (field (name "MANUFACTURER") "Lumex Opto/Components Inc.")
      )
      (libsource (lib "Celestial Altium Library - altium_library") (part "LED"))
    )
    (comp (ref "D113")
      (value "Yellow")
      (footprint "LED 0805_2012 YELLOW")
      (description "LED YELLOW CLEAR SMD")
      (fields
        (field (name "PART NUMBER") "SML-LX0805YC-TR")
        (field (name "MANUFACTURER") "Lumex Opto/Components Inc.")
      )
      (libsource (lib "Celestial Altium Library - altium_library") (part "LED"))
    )
    (comp (ref "D114")
      (value "Yellow")
      (footprint "LED 0805_2012 YELLOW")
      (description "LED YELLOW CLEAR SMD")
      (fields
        (field (name "PART NUMBER") "SML-LX0805YC-TR")
        (field (name "MANUFACTURER") "Lumex Opto/Components Inc.")
      )
      (libsource (lib "Celestial Altium Library - altium_library") (part "LED"))
    )
    (comp (ref "D115")
      (value "Yellow")
      (footprint "LED 0805_2012 YELLOW")
      (description "LED YELLOW CLEAR SMD")
      (fields
        (field (name "PART NUMBER") "SML-LX0805YC-TR")
        (field (name "MANUFACTURER") "Lumex Opto/Components Inc.")
      )
      (libsource (lib "Celestial Altium Library - altium_library") (part "LED"))
    )
    (comp (ref "D116")
      (value "Yellow")
      (footprint "LED 0805_2012 YELLOW")
      (description "LED YELLOW CLEAR SMD")
      (fields
        (field (name "PART NUMBER") "SML-LX0805YC-TR")
        (field (name "MANUFACTURER") "Lumex Opto/Components Inc.")
      )
      (libsource (lib "Celestial Altium Library - altium_library") (part "LED"))
    )
    (comp (ref "D117")
      (value "Yellow")
      (footprint "LED 0805_2012 YELLOW")
      (description "LED YELLOW CLEAR SMD")
      (fields
        (field (name "PART NUMBER") "SML-LX0805YC-TR")
        (field (name "MANUFACTURER") "Lumex Opto/Components Inc.")
      )
      (libsource (lib "Celestial Altium Library - altium_library") (part "LED"))
    )
    (comp (ref "D118")
      (value "Yellow")
      (footprint "LED 0805_2012 YELLOW")
      (description "LED YELLOW CLEAR SMD")
      (fields
        (field (name "PART NUMBER") "SML-LX0805YC-TR")
        (field (name "MANUFACTURER") "Lumex Opto/Components Inc.")
      )
      (libsource (lib "Celestial Altium Library - altium_library") (part "LED"))
    )
    (comp (ref "D119")
      (value "Yellow")
      (footprint "LED 0805_2012 YELLOW")
      (description "LED YELLOW CLEAR SMD")
      (fields
        (field (name "PART NUMBER") "SML-LX0805YC-TR")
        (field (name "MANUFACTURER") "Lumex Opto/Components Inc.")
      )
      (libsource (lib "Celestial Altium Library - altium_library") (part "LED"))
    )
    (comp (ref "D120")
      (value "Yellow")
      (footprint "LED 0805_2012 YELLOW")
      (description "LED YELLOW CLEAR SMD")
      (fields
        (field (name "PART NUMBER") "SML-LX0805YC-TR")
        (field (name "MANUFACTURER") "Lumex Opto/Components Inc.")
      )
      (libsource (lib "Celestial Altium Library - altium_library") (part "LED"))
    )
    (comp (ref "D121")
      (value "Yellow")
      (footprint "LED 0805_2012 YELLOW")
      (description "LED YELLOW CLEAR SMD")
      (fields
        (field (name "PART NUMBER") "SML-LX0805YC-TR")
        (field (name "MANUFACTURER") "Lumex Opto/Components Inc.")
      )
      (libsource (lib "Celestial Altium Library - altium_library") (part "LED"))
    )
    (comp (ref "D122")
      (value "Yellow")
      (footprint "LED 0805_2012 YELLOW")
      (description "LED YELLOW CLEAR SMD")
      (fields
        (field (name "PART NUMBER") "SML-LX0805YC-TR")
        (field (name "MANUFACTURER") "Lumex Opto/Components Inc.")
      )
      (libsource (lib "Celestial Altium Library - altium_library") (part "LED"))
    )
    (comp (ref "D123")
      (value "Yellow")
      (footprint "LED 0805_2012 YELLOW")
      (description "LED YELLOW CLEAR SMD")
      (fields
        (field (name "PART NUMBER") "SML-LX0805YC-TR")
        (field (name "MANUFACTURER") "Lumex Opto/Components Inc.")
      )
      (libsource (lib "Celestial Altium Library - altium_library") (part "LED"))
    )
    (comp (ref "D124")
      (value "Yellow")
      (footprint "LED 0805_2012 YELLOW")
      (description "LED YELLOW CLEAR SMD")
      (fields
        (field (name "PART NUMBER") "SML-LX0805YC-TR")
        (field (name "MANUFACTURER") "Lumex Opto/Components Inc.")
      )
      (libsource (lib "Celestial Altium Library - altium_library") (part "LED"))
    )
    (comp (ref "D125")
      (value "Yellow")
      (footprint "LED 0805_2012 YELLOW")
      (description "LED YELLOW CLEAR SMD")
      (fields
        (field (name "PART NUMBER") "SML-LX0805YC-TR")
        (field (name "MANUFACTURER") "Lumex Opto/Components Inc.")
      )
      (libsource (lib "Celestial Altium Library - altium_library") (part "LED"))
    )
    (comp (ref "D126")
      (value "Yellow")
      (footprint "LED 0805_2012 YELLOW")
      (description "LED YELLOW CLEAR SMD")
      (fields
        (field (name "PART NUMBER") "SML-LX0805YC-TR")
        (field (name "MANUFACTURER") "Lumex Opto/Components Inc.")
      )
      (libsource (lib "Celestial Altium Library - altium_library") (part "LED"))
    )
    (comp (ref "D127")
      (value "Yellow")
      (footprint "LED 0805_2012 YELLOW")
      (description "LED YELLOW CLEAR SMD")
      (fields
        (field (name "PART NUMBER") "SML-LX0805YC-TR")
        (field (name "MANUFACTURER") "Lumex Opto/Components Inc.")
      )
      (libsource (lib "Celestial Altium Library - altium_library") (part "LED"))
    )
    (comp (ref "D128")
      (value "Yellow")
      (footprint "LED 0805_2012 YELLOW")
      (description "LED YELLOW CLEAR SMD")
      (fields
        (field (name "PART NUMBER") "SML-LX0805YC-TR")
        (field (name "MANUFACTURER") "Lumex Opto/Components Inc.")
      )
      (libsource (lib "Celestial Altium Library - altium_library") (part "LED"))
    )
    (comp (ref "D129")
      (value "Yellow")
      (footprint "LED 0805_2012 YELLOW")
      (description "LED YELLOW CLEAR SMD")
      (fields
        (field (name "PART NUMBER") "SML-LX0805YC-TR")
        (field (name "MANUFACTURER") "Lumex Opto/Components Inc.")
      )
      (libsource (lib "Celestial Altium Library - altium_library") (part "LED"))
    )
    (comp (ref "D130")
      (value "Yellow")
      (footprint "LED 0805_2012 YELLOW")
      (description "LED YELLOW CLEAR SMD")
      (fields
        (field (name "PART NUMBER") "SML-LX0805YC-TR")
        (field (name "MANUFACTURER") "Lumex Opto/Components Inc.")
      )
      (libsource (lib "Celestial Altium Library - altium_library") (part "LED"))
    )
    (comp (ref "D131")
      (value "Yellow")
      (footprint "LED 0805_2012 YELLOW")
      (description "LED YELLOW CLEAR SMD")
      (fields
        (field (name "PART NUMBER") "SML-LX0805YC-TR")
        (field (name "MANUFACTURER") "Lumex Opto/Components Inc.")
      )
      (libsource (lib "Celestial Altium Library - altium_library") (part "LED"))
    )
    (comp (ref "D132")
      (value "Yellow")
      (footprint "LED 0805_2012 YELLOW")
      (description "LED YELLOW CLEAR SMD")
      (fields
        (field (name "PART NUMBER") "SML-LX0805YC-TR")
        (field (name "MANUFACTURER") "Lumex Opto/Components Inc.")
      )
      (libsource (lib "Celestial Altium Library - altium_library") (part "LED"))
    )
    (comp (ref "D133")
      (value "Yellow")
      (footprint "LED 0805_2012 YELLOW")
      (description "LED YELLOW CLEAR SMD")
      (fields
        (field (name "PART NUMBER") "SML-LX0805YC-TR")
        (field (name "MANUFACTURER") "Lumex Opto/Components Inc.")
      )
      (libsource (lib "Celestial Altium Library - altium_library") (part "LED"))
    )
    (comp (ref "D134")
      (value "Yellow")
      (footprint "LED 0805_2012 YELLOW")
      (description "LED YELLOW CLEAR SMD")
      (fields
        (field (name "PART NUMBER") "SML-LX0805YC-TR")
        (field (name "MANUFACTURER") "Lumex Opto/Components Inc.")
      )
      (libsource (lib "Celestial Altium Library - altium_library") (part "LED"))
    )
    (comp (ref "D135")
      (value "Yellow")
      (footprint "LED 0805_2012 YELLOW")
      (description "LED YELLOW CLEAR SMD")
      (fields
        (field (name "PART NUMBER") "SML-LX0805YC-TR")
        (field (name "MANUFACTURER") "Lumex Opto/Components Inc.")
      )
      (libsource (lib "Celestial Altium Library - altium_library") (part "LED"))
    )
    (comp (ref "D136")
      (value "Yellow")
      (footprint "LED 0805_2012 YELLOW")
      (description "LED YELLOW CLEAR SMD")
      (fields
        (field (name "PART NUMBER") "SML-LX0805YC-TR")
        (field (name "MANUFACTURER") "Lumex Opto/Components Inc.")
      )
      (libsource (lib "Celestial Altium Library - altium_library") (part "LED"))
    )
    (comp (ref "D137")
      (value "Yellow")
      (footprint "LED 0805_2012 YELLOW")
      (description "LED YELLOW CLEAR SMD")
      (fields
        (field (name "PART NUMBER") "SML-LX0805YC-TR")
        (field (name "MANUFACTURER") "Lumex Opto/Components Inc.")
      )
      (libsource (lib "Celestial Altium Library - altium_library") (part "LED"))
    )
    (comp (ref "D138")
      (value "Yellow")
      (footprint "LED 0805_2012 YELLOW")
      (description "LED YELLOW CLEAR SMD")
      (fields
        (field (name "PART NUMBER") "SML-LX0805YC-TR")
        (field (name "MANUFACTURER") "Lumex Opto/Components Inc.")
      )
      (libsource (lib "Celestial Altium Library - altium_library") (part "LED"))
    )
    (comp (ref "D139")
      (value "Yellow")
      (footprint "LED 0805_2012 YELLOW")
      (description "LED YELLOW CLEAR SMD")
      (fields
        (field (name "PART NUMBER") "SML-LX0805YC-TR")
        (field (name "MANUFACTURER") "Lumex Opto/Components Inc.")
      )
      (libsource (lib "Celestial Altium Library - altium_library") (part "LED"))
    )
    (comp (ref "D140")
      (value "Yellow")
      (footprint "LED 0805_2012 YELLOW")
      (description "LED YELLOW CLEAR SMD")
      (fields
        (field (name "PART NUMBER") "SML-LX0805YC-TR")
        (field (name "MANUFACTURER") "Lumex Opto/Components Inc.")
      )
      (libsource (lib "Celestial Altium Library - altium_library") (part "LED"))
    )
    (comp (ref "D141")
      (value "Yellow")
      (footprint "LED 0805_2012 YELLOW")
      (description "LED YELLOW CLEAR SMD")
      (fields
        (field (name "PART NUMBER") "SML-LX0805YC-TR")
        (field (name "MANUFACTURER") "Lumex Opto/Components Inc.")
      )
      (libsource (lib "Celestial Altium Library - altium_library") (part "LED"))
    )
    (comp (ref "D142")
      (value "Yellow")
      (footprint "LED 0805_2012 YELLOW")
      (description "LED YELLOW CLEAR SMD")
      (fields
        (field (name "PART NUMBER") "SML-LX0805YC-TR")
        (field (name "MANUFACTURER") "Lumex Opto/Components Inc.")
      )
      (libsource (lib "Celestial Altium Library - altium_library") (part "LED"))
    )
    (comp (ref "D143")
      (value "Yellow")
      (footprint "LED 0805_2012 YELLOW")
      (description "LED YELLOW CLEAR SMD")
      (fields
        (field (name "PART NUMBER") "SML-LX0805YC-TR")
        (field (name "MANUFACTURER") "Lumex Opto/Components Inc.")
      )
      (libsource (lib "Celestial Altium Library - altium_library") (part "LED"))
    )
    (comp (ref "D144")
      (value "Yellow")
      (footprint "LED 0805_2012 YELLOW")
      (description "LED YELLOW CLEAR SMD")
      (fields
        (field (name "PART NUMBER") "SML-LX0805YC-TR")
        (field (name "MANUFACTURER") "Lumex Opto/Components Inc.")
      )
      (libsource (lib "Celestial Altium Library - altium_library") (part "LED"))
    )
    (comp (ref "D145")
      (value "Yellow")
      (footprint "LED 0805_2012 YELLOW")
      (description "LED YELLOW CLEAR SMD")
      (fields
        (field (name "PART NUMBER") "SML-LX0805YC-TR")
        (field (name "MANUFACTURER") "Lumex Opto/Components Inc.")
      )
      (libsource (lib "Celestial Altium Library - altium_library") (part "LED"))
    )
    (comp (ref "D146")
      (value "Yellow")
      (footprint "LED 0805_2012 YELLOW")
      (description "LED YELLOW CLEAR SMD")
      (fields
        (field (name "PART NUMBER") "SML-LX0805YC-TR")
        (field (name "MANUFACTURER") "Lumex Opto/Components Inc.")
      )
      (libsource (lib "Celestial Altium Library - altium_library") (part "LED"))
    )
    (comp (ref "D147")
      (value "Yellow")
      (footprint "LED 0805_2012 YELLOW")
      (description "LED YELLOW CLEAR SMD")
      (fields
        (field (name "PART NUMBER") "SML-LX0805YC-TR")
        (field (name "MANUFACTURER") "Lumex Opto/Components Inc.")
      )
      (libsource (lib "Celestial Altium Library - altium_library") (part "LED"))
    )
    (comp (ref "D148")
      (value "Yellow")
      (footprint "LED 0805_2012 YELLOW")
      (description "LED YELLOW CLEAR SMD")
      (fields
        (field (name "PART NUMBER") "SML-LX0805YC-TR")
        (field (name "MANUFACTURER") "Lumex Opto/Components Inc.")
      )
      (libsource (lib "Celestial Altium Library - altium_library") (part "LED"))
    )
    (comp (ref "D149")
      (value "Yellow")
      (footprint "LED 0805_2012 YELLOW")
      (description "LED YELLOW CLEAR SMD")
      (fields
        (field (name "PART NUMBER") "SML-LX0805YC-TR")
        (field (name "MANUFACTURER") "Lumex Opto/Components Inc.")
      )
      (libsource (lib "Celestial Altium Library - altium_library") (part "LED"))
    )
    (comp (ref "D150")
      (value "Yellow")
      (footprint "LED 0805_2012 YELLOW")
      (description "LED YELLOW CLEAR SMD")
      (fields
        (field (name "PART NUMBER") "SML-LX0805YC-TR")
        (field (name "MANUFACTURER") "Lumex Opto/Components Inc.")
      )
      (libsource (lib "Celestial Altium Library - altium_library") (part "LED"))
    )
    (comp (ref "D151")
      (value "Yellow")
      (footprint "LED 0805_2012 YELLOW")
      (description "LED YELLOW CLEAR SMD")
      (fields
        (field (name "PART NUMBER") "SML-LX0805YC-TR")
        (field (name "MANUFACTURER") "Lumex Opto/Components Inc.")
      )
      (libsource (lib "Celestial Altium Library - altium_library") (part "LED"))
    )
    (comp (ref "P8")
      (value "Header 15")
      (footprint "HDR1X15")
      (description "Header, 15-Pin")
      (fields (field (name "PUBLISHER") "Altium Limited"))
      (libsource (lib "Miscellaneous Connectors") (part "Header 15"))
    )
    (comp (ref "P9")
      (value "Header 10")
      (footprint "HDR1X10")
      (description "Header, 10-Pin")
      (fields (field (name "PUBLISHER") "Altium Limited"))
      (libsource (lib "Miscellaneous Connectors") (part "Header 10"))
    )
    (comp (ref "R35")
      (value "68 Ohms")
      (footprint "RES 0603_1608")
      (description "CRGCQ 0603 68R 5%")
      (fields
        (field (name "PART NUMBER") "CRGCQ0603J68R")
        (field (name "MANUFACTURER") "TE Connectivity Passive Product")
      )
      (libsource (lib "Celestial Altium Library - altium_library") (part "Resistor"))
    )
    (comp (ref "R36")
      (value "68 Ohms")
      (footprint "RES 0603_1608")
      (description "CRGCQ 0603 68R 5%")
      (fields
        (field (name "PART NUMBER") "CRGCQ0603J68R")
        (field (name "MANUFACTURER") "TE Connectivity Passive Product")
      )
      (libsource (lib "Celestial Altium Library - altium_library") (part "Resistor"))
    )
    (comp (ref "R37")
      (value "68 Ohms")
      (footprint "RES 0603_1608")
      (description "CRGCQ 0603 68R 5%")
      (fields
        (field (name "PART NUMBER") "CRGCQ0603J68R")
        (field (name "MANUFACTURER") "TE Connectivity Passive Product")
      )
      (libsource (lib "Celestial Altium Library - altium_library") (part "Resistor"))
    )
    (comp (ref "R38")
      (value "68 Ohms")
      (footprint "RES 0603_1608")
      (description "CRGCQ 0603 68R 5%")
      (fields
        (field (name "PART NUMBER") "CRGCQ0603J68R")
        (field (name "MANUFACTURER") "TE Connectivity Passive Product")
      )
      (libsource (lib "Celestial Altium Library - altium_library") (part "Resistor"))
    )
    (comp (ref "R39")
      (value "68 Ohms")
      (footprint "RES 0603_1608")
      (description "CRGCQ 0603 68R 5%")
      (fields
        (field (name "PART NUMBER") "CRGCQ0603J68R")
        (field (name "MANUFACTURER") "TE Connectivity Passive Product")
      )
      (libsource (lib "Celestial Altium Library - altium_library") (part "Resistor"))
    )
    (comp (ref "R40")
      (value "68 Ohms")
      (footprint "RES 0603_1608")
      (description "CRGCQ 0603 68R 5%")
      (fields
        (field (name "PART NUMBER") "CRGCQ0603J68R")
        (field (name "MANUFACTURER") "TE Connectivity Passive Product")
      )
      (libsource (lib "Celestial Altium Library - altium_library") (part "Resistor"))
    )
    (comp (ref "R41")
      (value "68 Ohms")
      (footprint "RES 0603_1608")
      (description "CRGCQ 0603 68R 5%")
      (fields
        (field (name "PART NUMBER") "CRGCQ0603J68R")
        (field (name "MANUFACTURER") "TE Connectivity Passive Product")
      )
      (libsource (lib "Celestial Altium Library - altium_library") (part "Resistor"))
    )
    (comp (ref "R42")
      (value "68 Ohms")
      (footprint "RES 0603_1608")
      (description "CRGCQ 0603 68R 5%")
      (fields
        (field (name "PART NUMBER") "CRGCQ0603J68R")
        (field (name "MANUFACTURER") "TE Connectivity Passive Product")
      )
      (libsource (lib "Celestial Altium Library - altium_library") (part "Resistor"))
    )
    (comp (ref "R43")
      (value "68 Ohms")
      (footprint "RES 0603_1608")
      (description "CRGCQ 0603 68R 5%")
      (fields
        (field (name "PART NUMBER") "CRGCQ0603J68R")
        (field (name "MANUFACTURER") "TE Connectivity Passive Product")
      )
      (libsource (lib "Celestial Altium Library - altium_library") (part "Resistor"))
    )
    (comp (ref "R44")
      (value "68 Ohms")
      (footprint "RES 0603_1608")
      (description "CRGCQ 0603 68R 5%")
      (fields
        (field (name "PART NUMBER") "CRGCQ0603J68R")
        (field (name "MANUFACTURER") "TE Connectivity Passive Product")
      )
      (libsource (lib "Celestial Altium Library - altium_library") (part "Resistor"))
    )
    (comp (ref "R45")
      (value "68 Ohms")
      (footprint "RES 0603_1608")
      (description "CRGCQ 0603 68R 5%")
      (fields
        (field (name "PART NUMBER") "CRGCQ0603J68R")
        (field (name "MANUFACTURER") "TE Connectivity Passive Product")
      )
      (libsource (lib "Celestial Altium Library - altium_library") (part "Resistor"))
    )
    (comp (ref "R46")
      (value "68 Ohms")
      (footprint "RES 0603_1608")
      (description "CRGCQ 0603 68R 5%")
      (fields
        (field (name "PART NUMBER") "CRGCQ0603J68R")
        (field (name "MANUFACTURER") "TE Connectivity Passive Product")
      )
      (libsource (lib "Celestial Altium Library - altium_library") (part "Resistor"))
    )
    (comp (ref "R47")
      (value "68 Ohms")
      (footprint "RES 0603_1608")
      (description "CRGCQ 0603 68R 5%")
      (fields
        (field (name "PART NUMBER") "CRGCQ0603J68R")
        (field (name "MANUFACTURER") "TE Connectivity Passive Product")
      )
      (libsource (lib "Celestial Altium Library - altium_library") (part "Resistor"))
    )
    (comp (ref "R48")
      (value "68 Ohms")
      (footprint "RES 0603_1608")
      (description "CRGCQ 0603 68R 5%")
      (fields
        (field (name "PART NUMBER") "CRGCQ0603J68R")
        (field (name "MANUFACTURER") "TE Connectivity Passive Product")
      )
      (libsource (lib "Celestial Altium Library - altium_library") (part "Resistor"))
    )
    (comp (ref "R49")
      (value "68 Ohms")
      (footprint "RES 0603_1608")
      (description "CRGCQ 0603 68R 5%")
      (fields
        (field (name "PART NUMBER") "CRGCQ0603J68R")
        (field (name "MANUFACTURER") "TE Connectivity Passive Product")
      )
      (libsource (lib "Celestial Altium Library - altium_library") (part "Resistor"))
    )
  )
  (nets
    (net (code "1") (name "/1") (class "Default")
      (node (ref "D10") (pin "1") (pinfunction "1_1") (pintype "passive"))
      (node (ref "D11") (pin "1") (pinfunction "1_1") (pintype "passive"))
      (node (ref "D12") (pin "1") (pinfunction "1_1") (pintype "passive"))
      (node (ref "D13") (pin "1") (pinfunction "1_1") (pintype "passive"))
      (node (ref "D14") (pin "1") (pinfunction "1_1") (pintype "passive"))
      (node (ref "D15") (pin "1") (pinfunction "1_1") (pintype "passive"))
      (node (ref "D16") (pin "1") (pinfunction "1_1") (pintype "passive"))
      (node (ref "D2") (pin "1") (pinfunction "1_1") (pintype "passive"))
      (node (ref "D3") (pin "1") (pinfunction "1_1") (pintype "passive"))
      (node (ref "D4") (pin "1") (pinfunction "1_1") (pintype "passive"))
      (node (ref "D5") (pin "1") (pinfunction "1_1") (pintype "passive"))
      (node (ref "D6") (pin "1") (pinfunction "1_1") (pintype "passive"))
      (node (ref "D7") (pin "1") (pinfunction "1_1") (pintype "passive"))
      (node (ref "D8") (pin "1") (pinfunction "1_1") (pintype "passive"))
      (node (ref "D9") (pin "1") (pinfunction "1_1") (pintype "passive"))
      (node (ref "P9") (pin "1") (pinfunction "1_1") (pintype "passive"))
    )
    (net (code "2") (name "/2") (class "Default")
      (node (ref "D17") (pin "1") (pinfunction "1_1") (pintype "passive"))
      (node (ref "D18") (pin "1") (pinfunction "1_1") (pintype "passive"))
      (node (ref "D19") (pin "1") (pinfunction "1_1") (pintype "passive"))
      (node (ref "D20") (pin "1") (pinfunction "1_1") (pintype "passive"))
      (node (ref "D21") (pin "1") (pinfunction "1_1") (pintype "passive"))
      (node (ref "D22") (pin "1") (pinfunction "1_1") (pintype "passive"))
      (node (ref "D23") (pin "1") (pinfunction "1_1") (pintype "passive"))
      (node (ref "D24") (pin "1") (pinfunction "1_1") (pintype "passive"))
      (node (ref "D25") (pin "1") (pinfunction "1_1") (pintype "passive"))
      (node (ref "D26") (pin "1") (pinfunction "1_1") (pintype "passive"))
      (node (ref "D27") (pin "1") (pinfunction "1_1") (pintype "passive"))
      (node (ref "D28") (pin "1") (pinfunction "1_1") (pintype "passive"))
      (node (ref "D29") (pin "1") (pinfunction "1_1") (pintype "passive"))
      (node (ref "D30") (pin "1") (pinfunction "1_1") (pintype "passive"))
      (node (ref "D31") (pin "1") (pinfunction "1_1") (pintype "passive"))
      (node (ref "P9") (pin "2") (pinfunction "2_2") (pintype "passive"))
    )
    (net (code "3") (name "/3") (class "Default")
      (node (ref "D32") (pin "1") (pinfunction "1_1") (pintype "passive"))
      (node (ref "D33") (pin "1") (pinfunction "1_1") (pintype "passive"))
      (node (ref "D34") (pin "1") (pinfunction "1_1") (pintype "passive"))
      (node (ref "D35") (pin "1") (pinfunction "1_1") (pintype "passive"))
      (node (ref "D36") (pin "1") (pinfunction "1_1") (pintype "passive"))
      (node (ref "D37") (pin "1") (pinfunction "1_1") (pintype "passive"))
      (node (ref "D38") (pin "1") (pinfunction "1_1") (pintype "passive"))
      (node (ref "D39") (pin "1") (pinfunction "1_1") (pintype "passive"))
      (node (ref "D40") (pin "1") (pinfunction "1_1") (pintype "passive"))
      (node (ref "D41") (pin "1") (pinfunction "1_1") (pintype "passive"))
      (node (ref "D42") (pin "1") (pinfunction "1_1") (pintype "passive"))
      (node (ref "D43") (pin "1") (pinfunction "1_1") (pintype "passive"))
      (node (ref "D44") (pin "1") (pinfunction "1_1") (pintype "passive"))
      (node (ref "D45") (pin "1") (pinfunction "1_1") (pintype "passive"))
      (node (ref "D46") (pin "1") (pinfunction "1_1") (pintype "passive"))
      (node (ref "P9") (pin "3") (pinfunction "3_3") (pintype "passive"))
    )
    (net (code "4") (name "/4") (class "Default")
      (node (ref "D47") (pin "1") (pinfunction "1_1") (pintype "passive"))
      (node (ref "D48") (pin "1") (pinfunction "1_1") (pintype "passive"))
      (node (ref "D49") (pin "1") (pinfunction "1_1") (pintype "passive"))
      (node (ref "D50") (pin "1") (pinfunction "1_1") (pintype "passive"))
      (node (ref "D51") (pin "1") (pinfunction "1_1") (pintype "passive"))
      (node (ref "D52") (pin "1") (pinfunction "1_1") (pintype "passive"))
      (node (ref "D53") (pin "1") (pinfunction "1_1") (pintype "passive"))
      (node (ref "D54") (pin "1") (pinfunction "1_1") (pintype "passive"))
      (node (ref "D55") (pin "1") (pinfunction "1_1") (pintype "passive"))
      (node (ref "D56") (pin "1") (pinfunction "1_1") (pintype "passive"))
      (node (ref "D57") (pin "1") (pinfunction "1_1") (pintype "passive"))
      (node (ref "D58") (pin "1") (pinfunction "1_1") (pintype "passive"))
      (node (ref "D59") (pin "1") (pinfunction "1_1") (pintype "passive"))
      (node (ref "D60") (pin "1") (pinfunction "1_1") (pintype "passive"))
      (node (ref "D61") (pin "1") (pinfunction "1_1") (pintype "passive"))
      (node (ref "P9") (pin "4") (pinfunction "4_4") (pintype "passive"))
    )
    (net (code "5") (name "/5") (class "Default")
      (node (ref "D62") (pin "1") (pinfunction "1_1") (pintype "passive"))
      (node (ref "D63") (pin "1") (pinfunction "1_1") (pintype "passive"))
      (node (ref "D64") (pin "1") (pinfunction "1_1") (pintype "passive"))
      (node (ref "D65") (pin "1") (pinfunction "1_1") (pintype "passive"))
      (node (ref "D66") (pin "1") (pinfunction "1_1") (pintype "passive"))
      (node (ref "D67") (pin "1") (pinfunction "1_1") (pintype "passive"))
      (node (ref "D68") (pin "1") (pinfunction "1_1") (pintype "passive"))
      (node (ref "D69") (pin "1") (pinfunction "1_1") (pintype "passive"))
      (node (ref "D70") (pin "1") (pinfunction "1_1") (pintype "passive"))
      (node (ref "D71") (pin "1") (pinfunction "1_1") (pintype "passive"))
      (node (ref "D72") (pin "1") (pinfunction "1_1") (pintype "passive"))
      (node (ref "D73") (pin "1") (pinfunction "1_1") (pintype "passive"))
      (node (ref "D74") (pin "1") (pinfunction "1_1") (pintype "passive"))
      (node (ref "D75") (pin "1") (pinfunction "1_1") (pintype "passive"))
      (node (ref "D76") (pin "1") (pinfunction "1_1") (pintype "passive"))
      (node (ref "P9") (pin "5") (pinfunction "5_5") (pintype "passive"))
    )
    (net (code "6") (name "/6") (class "Default")
      (node (ref "D77") (pin "1") (pinfunction "1_1") (pintype "passive"))
      (node (ref "D78") (pin "1") (pinfunction "1_1") (pintype "passive"))
      (node (ref "D79") (pin "1") (pinfunction "1_1") (pintype "passive"))
      (node (ref "D80") (pin "1") (pinfunction "1_1") (pintype "passive"))
      (node (ref "D81") (pin "1") (pinfunction "1_1") (pintype "passive"))
      (node (ref "D82") (pin "1") (pinfunction "1_1") (pintype "passive"))
      (node (ref "D83") (pin "1") (pinfunction "1_1") (pintype "passive"))
      (node (ref "D84") (pin "1") (pinfunction "1_1") (pintype "passive"))
      (node (ref "D85") (pin "1") (pinfunction "1_1") (pintype "passive"))
      (node (ref "D86") (pin "1") (pinfunction "1_1") (pintype "passive"))
      (node (ref "D87") (pin "1") (pinfunction "1_1") (pintype "passive"))
      (node (ref "D88") (pin "1") (pinfunction "1_1") (pintype "passive"))
      (node (ref "D89") (pin "1") (pinfunction "1_1") (pintype "passive"))
      (node (ref "D90") (pin "1") (pinfunction "1_1") (pintype "passive"))
      (node (ref "D91") (pin "1") (pinfunction "1_1") (pintype "passive"))
      (node (ref "P9") (pin "6") (pinfunction "6_6") (pintype "passive"))
    )
    (net (code "7") (name "/7") (class "Default")
      (node (ref "D100") (pin "1") (pinfunction "1_1") (pintype "passive"))
      (node (ref "D101") (pin "1") (pinfunction "1_1") (pintype "passive"))
      (node (ref "D102") (pin "1") (pinfunction "1_1") (pintype "passive"))
      (node (ref "D103") (pin "1") (pinfunction "1_1") (pintype "passive"))
      (node (ref "D104") (pin "1") (pinfunction "1_1") (pintype "passive"))
      (node (ref "D105") (pin "1") (pinfunction "1_1") (pintype "passive"))
      (node (ref "D106") (pin "1") (pinfunction "1_1") (pintype "passive"))
      (node (ref "D92") (pin "1") (pinfunction "1_1") (pintype "passive"))
      (node (ref "D93") (pin "1") (pinfunction "1_1") (pintype "passive"))
      (node (ref "D94") (pin "1") (pinfunction "1_1") (pintype "passive"))
      (node (ref "D95") (pin "1") (pinfunction "1_1") (pintype "passive"))
      (node (ref "D96") (pin "1") (pinfunction "1_1") (pintype "passive"))
      (node (ref "D97") (pin "1") (pinfunction "1_1") (pintype "passive"))
      (node (ref "D98") (pin "1") (pinfunction "1_1") (pintype "passive"))
      (node (ref "D99") (pin "1") (pinfunction "1_1") (pintype "passive"))
      (node (ref "P9") (pin "7") (pinfunction "7_7") (pintype "passive"))
    )
    (net (code "8") (name "/8") (class "Default")
      (node (ref "D107") (pin "1") (pinfunction "1_1") (pintype "passive"))
      (node (ref "D108") (pin "1") (pinfunction "1_1") (pintype "passive"))
      (node (ref "D109") (pin "1") (pinfunction "1_1") (pintype "passive"))
      (node (ref "D110") (pin "1") (pinfunction "1_1") (pintype "passive"))
      (node (ref "D111") (pin "1") (pinfunction "1_1") (pintype "passive"))
      (node (ref "D112") (pin "1") (pinfunction "1_1") (pintype "passive"))
      (node (ref "D113") (pin "1") (pinfunction "1_1") (pintype "passive"))
      (node (ref "D114") (pin "1") (pinfunction "1_1") (pintype "passive"))
      (node (ref "D115") (pin "1") (pinfunction "1_1") (pintype "passive"))
      (node (ref "D116") (pin "1") (pinfunction "1_1") (pintype "passive"))
      (node (ref "D117") (pin "1") (pinfunction "1_1") (pintype "passive"))
      (node (ref "D118") (pin "1") (pinfunction "1_1") (pintype "passive"))
      (node (ref "D119") (pin "1") (pinfunction "1_1") (pintype "passive"))
      (node (ref "D120") (pin "1") (pinfunction "1_1") (pintype "passive"))
      (node (ref "D121") (pin "1") (pinfunction "1_1") (pintype "passive"))
      (node (ref "P9") (pin "8") (pinfunction "8_8") (pintype "passive"))
    )
    (net (code "9") (name "/9") (class "Default")
      (node (ref "D122") (pin "1") (pinfunction "1_1") (pintype "passive"))
      (node (ref "D123") (pin "1") (pinfunction "1_1") (pintype "passive"))
      (node (ref "D124") (pin "1") (pinfunction "1_1") (pintype "passive"))
      (node (ref "D125") (pin "1") (pinfunction "1_1") (pintype "passive"))
      (node (ref "D126") (pin "1") (pinfunction "1_1") (pintype "passive"))
      (node (ref "D127") (pin "1") (pinfunction "1_1") (pintype "passive"))
      (node (ref "D128") (pin "1") (pinfunction "1_1") (pintype "passive"))
      (node (ref "D129") (pin "1") (pinfunction "1_1") (pintype "passive"))
      (node (ref "D130") (pin "1") (pinfunction "1_1") (pintype "passive"))
      (node (ref "D131") (pin "1") (pinfunction "1_1") (pintype "passive"))
      (node (ref "D132") (pin "1") (pinfunction "1_1") (pintype "passive"))
      (node (ref "D133") (pin "1") (pinfunction "1_1") (pintype "passive"))
      (node (ref "D134") (pin "1") (pinfunction "1_1") (pintype "passive"))
      (node (ref "D135") (pin "1") (pinfunction "1_1") (pintype "passive"))
      (node (ref "D136") (pin "1") (pinfunction "1_1") (pintype "passive"))
      (node (ref "P9") (pin "9") (pinfunction "9_9") (pintype "passive"))
    )
    (net (code "10") (name "/10") (class "Default")
      (node (ref "D137") (pin "1") (pinfunction "1_1") (pintype "passive"))
      (node (ref "D138") (pin "1") (pinfunction "1_1") (pintype "passive"))
      (node (ref "D139") (pin "1") (pinfunction "1_1") (pintype "passive"))
      (node (ref "D140") (pin "1") (pinfunction "1_1") (pintype "passive"))
      (node (ref "D141") (pin "1") (pinfunction "1_1") (pintype "passive"))
      (node (ref "D142") (pin "1") (pinfunction "1_1") (pintype "passive"))
      (node (ref "D143") (pin "1") (pinfunction "1_1") (pintype "passive"))
      (node (ref "D144") (pin "1") (pinfunction "1_1") (pintype "passive"))
      (node (ref "D145") (pin "1") (pinfunction "1_1") (pintype "passive"))
      (node (ref "D146") (pin "1") (pinfunction "1_1") (pintype "passive"))
      (node (ref "D147") (pin "1") (pinfunction "1_1") (pintype "passive"))
      (node (ref "D148") (pin "1") (pinfunction "1_1") (pintype "passive"))
      (node (ref "D149") (pin "1") (pinfunction "1_1") (pintype "passive"))
      (node (ref "D150") (pin "1") (pinfunction "1_1") (pintype "passive"))
      (node (ref "D151") (pin "1") (pinfunction "1_1") (pintype "passive"))
      (node (ref "P9") (pin "10") (pinfunction "10_10") (pintype "passive"))
    )
    (net (code "11") (name "/A") (class "Default")
      (node (ref "P8") (pin "15") (pinfunction "15_15") (pintype "passive"))
      (node (ref "R35") (pin "2") (pinfunction "2_2") (pintype "passive"))
    )
    (net (code "12") (name "/B") (class "Default")
      (node (ref "P8") (pin "14") (pinfunction "14_14") (pintype "passive"))
      (node (ref "R36") (pin "2") (pinfunction "2_2") (pintype "passive"))
    )
    (net (code "13") (name "/C") (class "Default")
      (node (ref "P8") (pin "13") (pinfunction "13_13") (pintype "passive"))
      (node (ref "R37") (pin "2") (pinfunction "2_2") (pintype "passive"))
    )
    (net (code "14") (name "/D") (class "Default")
      (node (ref "P8") (pin "12") (pinfunction "12_12") (pintype "passive"))
      (node (ref "R38") (pin "2") (pinfunction "2_2") (pintype "passive"))
    )
    (net (code "15") (name "/E") (class "Default")
      (node (ref "P8") (pin "11") (pinfunction "11_11") (pintype "passive"))
      (node (ref "R39") (pin "2") (pinfunction "2_2") (pintype "passive"))
    )
    (net (code "16") (name "/F") (class "Default")
      (node (ref "P8") (pin "10") (pinfunction "10_10") (pintype "passive"))
      (node (ref "R40") (pin "2") (pinfunction "2_2") (pintype "passive"))
    )
    (net (code "17") (name "/G") (class "Default")
      (node (ref "P8") (pin "9") (pinfunction "9_9") (pintype "passive"))
      (node (ref "R41") (pin "2") (pinfunction "2_2") (pintype "passive"))
    )
    (net (code "18") (name "/H") (class "Default")
      (node (ref "P8") (pin "8") (pinfunction "8_8") (pintype "passive"))
      (node (ref "R42") (pin "2") (pinfunction "2_2") (pintype "passive"))
    )
    (net (code "19") (name "/I") (class "Default")
      (node (ref "P8") (pin "7") (pinfunction "7_7") (pintype "passive"))
      (node (ref "R43") (pin "2") (pinfunction "2_2") (pintype "passive"))
    )
    (net (code "20") (name "/J") (class "Default")
      (node (ref "P8") (pin "6") (pinfunction "6_6") (pintype "passive"))
      (node (ref "R44") (pin "2") (pinfunction "2_2") (pintype "passive"))
    )
    (net (code "21") (name "/K") (class "Default")
      (node (ref "P8") (pin "5") (pinfunction "5_5") (pintype "passive"))
      (node (ref "R45") (pin "2") (pinfunction "2_2") (pintype "passive"))
    )
    (net (code "22") (name "/L") (class "Default")
      (node (ref "P8") (pin "4") (pinfunction "4_4") (pintype "passive"))
      (node (ref "R46") (pin "2") (pinfunction "2_2") (pintype "passive"))
    )
    (net (code "23") (name "/M") (class "Default")
      (node (ref "P8") (pin "3") (pinfunction "3_3") (pintype "passive"))
      (node (ref "R47") (pin "2") (pinfunction "2_2") (pintype "passive"))
    )
    (net (code "24") (name "/N") (class "Default")
      (node (ref "P8") (pin "2") (pinfunction "2_2") (pintype "passive"))
      (node (ref "R48") (pin "2") (pinfunction "2_2") (pintype "passive"))
    )
    (net (code "25") (name "/O") (class "Default")
      (node (ref "P8") (pin "1") (pinfunction "1_1") (pintype "passive"))
      (node (ref "R49") (pin "2") (pinfunction "2_2") (pintype "passive"))
    )
    (net (code "26") (name "Net-(D10-Pad2)") (class "Default")
      (node (ref "D10") (pin "2") (pinfunction "2_2") (pintype "passive"))
      (node (ref "D100") (pin "2") (pinfunction "2_2") (pintype "passive"))
      (node (ref "D115") (pin "2") (pinfunction "2_2") (pintype "passive"))
      (node (ref "D130") (pin "2") (pinfunction "2_2") (pintype "passive"))
      (node (ref "D145") (pin "2") (pinfunction "2_2") (pintype "passive"))
      (node (ref "D25") (pin "2") (pinfunction "2_2") (pintype "passive"))
      (node (ref "D40") (pin "2") (pinfunction "2_2") (pintype "passive"))
      (node (ref "D55") (pin "2") (pinfunction "2_2") (pintype "passive"))
      (node (ref "D70") (pin "2") (pinfunction "2_2") (pintype "passive"))
      (node (ref "D85") (pin "2") (pinfunction "2_2") (pintype "passive"))
      (node (ref "R43") (pin "1") (pinfunction "1_1") (pintype "passive"))
    )
    (net (code "27") (name "Net-(D101-Pad2)") (class "Default")
      (node (ref "D101") (pin "2") (pinfunction "2_2") (pintype "passive"))
      (node (ref "D11") (pin "2") (pinfunction "2_2") (pintype "passive"))
      (node (ref "D116") (pin "2") (pinfunction "2_2") (pintype "passive"))
      (node (ref "D131") (pin "2") (pinfunction "2_2") (pintype "passive"))
      (node (ref "D146") (pin "2") (pinfunction "2_2") (pintype "passive"))
      (node (ref "D26") (pin "2") (pinfunction "2_2") (pintype "passive"))
      (node (ref "D41") (pin "2") (pinfunction "2_2") (pintype "passive"))
      (node (ref "D56") (pin "2") (pinfunction "2_2") (pintype "passive"))
      (node (ref "D71") (pin "2") (pinfunction "2_2") (pintype "passive"))
      (node (ref "D86") (pin "2") (pinfunction "2_2") (pintype "passive"))
      (node (ref "R44") (pin "1") (pinfunction "1_1") (pintype "passive"))
    )
    (net (code "28") (name "Net-(D102-Pad2)") (class "Default")
      (node (ref "D102") (pin "2") (pinfunction "2_2") (pintype "passive"))
      (node (ref "D117") (pin "2") (pinfunction "2_2") (pintype "passive"))
      (node (ref "D12") (pin "2") (pinfunction "2_2") (pintype "passive"))
      (node (ref "D132") (pin "2") (pinfunction "2_2") (pintype "passive"))
      (node (ref "D147") (pin "2") (pinfunction "2_2") (pintype "passive"))
      (node (ref "D27") (pin "2") (pinfunction "2_2") (pintype "passive"))
      (node (ref "D42") (pin "2") (pinfunction "2_2") (pintype "passive"))
      (node (ref "D57") (pin "2") (pinfunction "2_2") (pintype "passive"))
      (node (ref "D72") (pin "2") (pinfunction "2_2") (pintype "passive"))
      (node (ref "D87") (pin "2") (pinfunction "2_2") (pintype "passive"))
      (node (ref "R45") (pin "1") (pinfunction "1_1") (pintype "passive"))
    )
    (net (code "29") (name "Net-(D103-Pad2)") (class "Default")
      (node (ref "D103") (pin "2") (pinfunction "2_2") (pintype "passive"))
      (node (ref "D118") (pin "2") (pinfunction "2_2") (pintype "passive"))
      (node (ref "D13") (pin "2") (pinfunction "2_2") (pintype "passive"))
      (node (ref "D133") (pin "2") (pinfunction "2_2") (pintype "passive"))
      (node (ref "D148") (pin "2") (pinfunction "2_2") (pintype "passive"))
      (node (ref "D28") (pin "2") (pinfunction "2_2") (pintype "passive"))
      (node (ref "D43") (pin "2") (pinfunction "2_2") (pintype "passive"))
      (node (ref "D58") (pin "2") (pinfunction "2_2") (pintype "passive"))
      (node (ref "D73") (pin "2") (pinfunction "2_2") (pintype "passive"))
      (node (ref "D88") (pin "2") (pinfunction "2_2") (pintype "passive"))
      (node (ref "R46") (pin "1") (pinfunction "1_1") (pintype "passive"))
    )
    (net (code "30") (name "Net-(D104-Pad2)") (class "Default")
      (node (ref "D104") (pin "2") (pinfunction "2_2") (pintype "passive"))
      (node (ref "D119") (pin "2") (pinfunction "2_2") (pintype "passive"))
      (node (ref "D134") (pin "2") (pinfunction "2_2") (pintype "passive"))
      (node (ref "D14") (pin "2") (pinfunction "2_2") (pintype "passive"))
      (node (ref "D149") (pin "2") (pinfunction "2_2") (pintype "passive"))
      (node (ref "D29") (pin "2") (pinfunction "2_2") (pintype "passive"))
      (node (ref "D44") (pin "2") (pinfunction "2_2") (pintype "passive"))
      (node (ref "D59") (pin "2") (pinfunction "2_2") (pintype "passive"))
      (node (ref "D74") (pin "2") (pinfunction "2_2") (pintype "passive"))
      (node (ref "D89") (pin "2") (pinfunction "2_2") (pintype "passive"))
      (node (ref "R47") (pin "1") (pinfunction "1_1") (pintype "passive"))
    )
    (net (code "31") (name "Net-(D105-Pad2)") (class "Default")
      (node (ref "D105") (pin "2") (pinfunction "2_2") (pintype "passive"))
      (node (ref "D120") (pin "2") (pinfunction "2_2") (pintype "passive"))
      (node (ref "D135") (pin "2") (pinfunction "2_2") (pintype "passive"))
      (node (ref "D15") (pin "2") (pinfunction "2_2") (pintype "passive"))
      (node (ref "D150") (pin "2") (pinfunction "2_2") (pintype "passive"))
      (node (ref "D30") (pin "2") (pinfunction "2_2") (pintype "passive"))
      (node (ref "D45") (pin "2") (pinfunction "2_2") (pintype "passive"))
      (node (ref "D60") (pin "2") (pinfunction "2_2") (pintype "passive"))
      (node (ref "D75") (pin "2") (pinfunction "2_2") (pintype "passive"))
      (node (ref "D90") (pin "2") (pinfunction "2_2") (pintype "passive"))
      (node (ref "R48") (pin "1") (pinfunction "1_1") (pintype "passive"))
    )
    (net (code "32") (name "Net-(D106-Pad2)") (class "Default")
      (node (ref "D106") (pin "2") (pinfunction "2_2") (pintype "passive"))
      (node (ref "D121") (pin "2") (pinfunction "2_2") (pintype "passive"))
      (node (ref "D136") (pin "2") (pinfunction "2_2") (pintype "passive"))
      (node (ref "D151") (pin "2") (pinfunction "2_2") (pintype "passive"))
      (node (ref "D16") (pin "2") (pinfunction "2_2") (pintype "passive"))
      (node (ref "D31") (pin "2") (pinfunction "2_2") (pintype "passive"))
      (node (ref "D46") (pin "2") (pinfunction "2_2") (pintype "passive"))
      (node (ref "D61") (pin "2") (pinfunction "2_2") (pintype "passive"))
      (node (ref "D76") (pin "2") (pinfunction "2_2") (pintype "passive"))
      (node (ref "D91") (pin "2") (pinfunction "2_2") (pintype "passive"))
      (node (ref "R49") (pin "1") (pinfunction "1_1") (pintype "passive"))
    )
    (net (code "33") (name "Net-(D107-Pad2)") (class "Default")
      (node (ref "D107") (pin "2") (pinfunction "2_2") (pintype "passive"))
      (node (ref "D122") (pin "2") (pinfunction "2_2") (pintype "passive"))
      (node (ref "D137") (pin "2") (pinfunction "2_2") (pintype "passive"))
      (node (ref "D17") (pin "2") (pinfunction "2_2") (pintype "passive"))
      (node (ref "D2") (pin "2") (pinfunction "2_2") (pintype "passive"))
      (node (ref "D32") (pin "2") (pinfunction "2_2") (pintype "passive"))
      (node (ref "D47") (pin "2") (pinfunction "2_2") (pintype "passive"))
      (node (ref "D62") (pin "2") (pinfunction "2_2") (pintype "passive"))
      (node (ref "D77") (pin "2") (pinfunction "2_2") (pintype "passive"))
      (node (ref "D92") (pin "2") (pinfunction "2_2") (pintype "passive"))
      (node (ref "R35") (pin "1") (pinfunction "1_1") (pintype "passive"))
    )
    (net (code "34") (name "Net-(D108-Pad2)") (class "Default")
      (node (ref "D108") (pin "2") (pinfunction "2_2") (pintype "passive"))
      (node (ref "D123") (pin "2") (pinfunction "2_2") (pintype "passive"))
      (node (ref "D138") (pin "2") (pinfunction "2_2") (pintype "passive"))
      (node (ref "D18") (pin "2") (pinfunction "2_2") (pintype "passive"))
      (node (ref "D3") (pin "2") (pinfunction "2_2") (pintype "passive"))
      (node (ref "D33") (pin "2") (pinfunction "2_2") (pintype "passive"))
      (node (ref "D48") (pin "2") (pinfunction "2_2") (pintype "passive"))
      (node (ref "D63") (pin "2") (pinfunction "2_2") (pintype "passive"))
      (node (ref "D78") (pin "2") (pinfunction "2_2") (pintype "passive"))
      (node (ref "D93") (pin "2") (pinfunction "2_2") (pintype "passive"))
      (node (ref "R36") (pin "1") (pinfunction "1_1") (pintype "passive"))
    )
    (net (code "35") (name "Net-(D109-Pad2)") (class "Default")
      (node (ref "D109") (pin "2") (pinfunction "2_2") (pintype "passive"))
      (node (ref "D124") (pin "2") (pinfunction "2_2") (pintype "passive"))
      (node (ref "D139") (pin "2") (pinfunction "2_2") (pintype "passive"))
      (node (ref "D19") (pin "2") (pinfunction "2_2") (pintype "passive"))
      (node (ref "D34") (pin "2") (pinfunction "2_2") (pintype "passive"))
      (node (ref "D4") (pin "2") (pinfunction "2_2") (pintype "passive"))
      (node (ref "D49") (pin "2") (pinfunction "2_2") (pintype "passive"))
      (node (ref "D64") (pin "2") (pinfunction "2_2") (pintype "passive"))
      (node (ref "D79") (pin "2") (pinfunction "2_2") (pintype "passive"))
      (node (ref "D94") (pin "2") (pinfunction "2_2") (pintype "passive"))
      (node (ref "R37") (pin "1") (pinfunction "1_1") (pintype "passive"))
    )
    (net (code "36") (name "Net-(D110-Pad2)") (class "Default")
      (node (ref "D110") (pin "2") (pinfunction "2_2") (pintype "passive"))
      (node (ref "D125") (pin "2") (pinfunction "2_2") (pintype "passive"))
      (node (ref "D140") (pin "2") (pinfunction "2_2") (pintype "passive"))
      (node (ref "D20") (pin "2") (pinfunction "2_2") (pintype "passive"))
      (node (ref "D35") (pin "2") (pinfunction "2_2") (pintype "passive"))
      (node (ref "D5") (pin "2") (pinfunction "2_2") (pintype "passive"))
      (node (ref "D50") (pin "2") (pinfunction "2_2") (pintype "passive"))
      (node (ref "D65") (pin "2") (pinfunction "2_2") (pintype "passive"))
      (node (ref "D80") (pin "2") (pinfunction "2_2") (pintype "passive"))
      (node (ref "D95") (pin "2") (pinfunction "2_2") (pintype "passive"))
      (node (ref "R38") (pin "1") (pinfunction "1_1") (pintype "passive"))
    )
    (net (code "37") (name "Net-(D111-Pad2)") (class "Default")
      (node (ref "D111") (pin "2") (pinfunction "2_2") (pintype "passive"))
      (node (ref "D126") (pin "2") (pinfunction "2_2") (pintype "passive"))
      (node (ref "D141") (pin "2") (pinfunction "2_2") (pintype "passive"))
      (node (ref "D21") (pin "2") (pinfunction "2_2") (pintype "passive"))
      (node (ref "D36") (pin "2") (pinfunction "2_2") (pintype "passive"))
      (node (ref "D51") (pin "2") (pinfunction "2_2") (pintype "passive"))
      (node (ref "D6") (pin "2") (pinfunction "2_2") (pintype "passive"))
      (node (ref "D66") (pin "2") (pinfunction "2_2") (pintype "passive"))
      (node (ref "D81") (pin "2") (pinfunction "2_2") (pintype "passive"))
      (node (ref "D96") (pin "2") (pinfunction "2_2") (pintype "passive"))
      (node (ref "R39") (pin "1") (pinfunction "1_1") (pintype "passive"))
    )
    (net (code "38") (name "Net-(D112-Pad2)") (class "Default")
      (node (ref "D112") (pin "2") (pinfunction "2_2") (pintype "passive"))
      (node (ref "D127") (pin "2") (pinfunction "2_2") (pintype "passive"))
      (node (ref "D142") (pin "2") (pinfunction "2_2") (pintype "passive"))
      (node (ref "D22") (pin "2") (pinfunction "2_2") (pintype "passive"))
      (node (ref "D37") (pin "2") (pinfunction "2_2") (pintype "passive"))
      (node (ref "D52") (pin "2") (pinfunction "2_2") (pintype "passive"))
      (node (ref "D67") (pin "2") (pinfunction "2_2") (pintype "passive"))
      (node (ref "D7") (pin "2") (pinfunction "2_2") (pintype "passive"))
      (node (ref "D82") (pin "2") (pinfunction "2_2") (pintype "passive"))
      (node (ref "D97") (pin "2") (pinfunction "2_2") (pintype "passive"))
      (node (ref "R40") (pin "1") (pinfunction "1_1") (pintype "passive"))
    )
    (net (code "39") (name "Net-(D113-Pad2)") (class "Default")
      (node (ref "D113") (pin "2") (pinfunction "2_2") (pintype "passive"))
      (node (ref "D128") (pin "2") (pinfunction "2_2") (pintype "passive"))
      (node (ref "D143") (pin "2") (pinfunction "2_2") (pintype "passive"))
      (node (ref "D23") (pin "2") (pinfunction "2_2") (pintype "passive"))
      (node (ref "D38") (pin "2") (pinfunction "2_2") (pintype "passive"))
      (node (ref "D53") (pin "2") (pinfunction "2_2") (pintype "passive"))
      (node (ref "D68") (pin "2") (pinfunction "2_2") (pintype "passive"))
      (node (ref "D8") (pin "2") (pinfunction "2_2") (pintype "passive"))
      (node (ref "D83") (pin "2") (pinfunction "2_2") (pintype "passive"))
      (node (ref "D98") (pin "2") (pinfunction "2_2") (pintype "passive"))
      (node (ref "R41") (pin "1") (pinfunction "1_1") (pintype "passive"))
    )
    (net (code "40") (name "Net-(D114-Pad2)") (class "Default")
      (node (ref "D114") (pin "2") (pinfunction "2_2") (pintype "passive"))
      (node (ref "D129") (pin "2") (pinfunction "2_2") (pintype "passive"))
      (node (ref "D144") (pin "2") (pinfunction "2_2") (pintype "passive"))
      (node (ref "D24") (pin "2") (pinfunction "2_2") (pintype "passive"))
      (node (ref "D39") (pin "2") (pinfunction "2_2") (pintype "passive"))
      (node (ref "D54") (pin "2") (pinfunction "2_2") (pintype "passive"))
      (node (ref "D69") (pin "2") (pinfunction "2_2") (pintype "passive"))
      (node (ref "D84") (pin "2") (pinfunction "2_2") (pintype "passive"))
      (node (ref "D9") (pin "2") (pinfunction "2_2") (pintype "passive"))
      (node (ref "D99") (pin "2") (pinfunction "2_2") (pintype "passive"))
      (node (ref "R42") (pin "1") (pinfunction "1_1") (pintype "passive"))
    )
  )
)
